# MotorControl_M.net
KiCad netlist of a schematic drawn in EAGLE
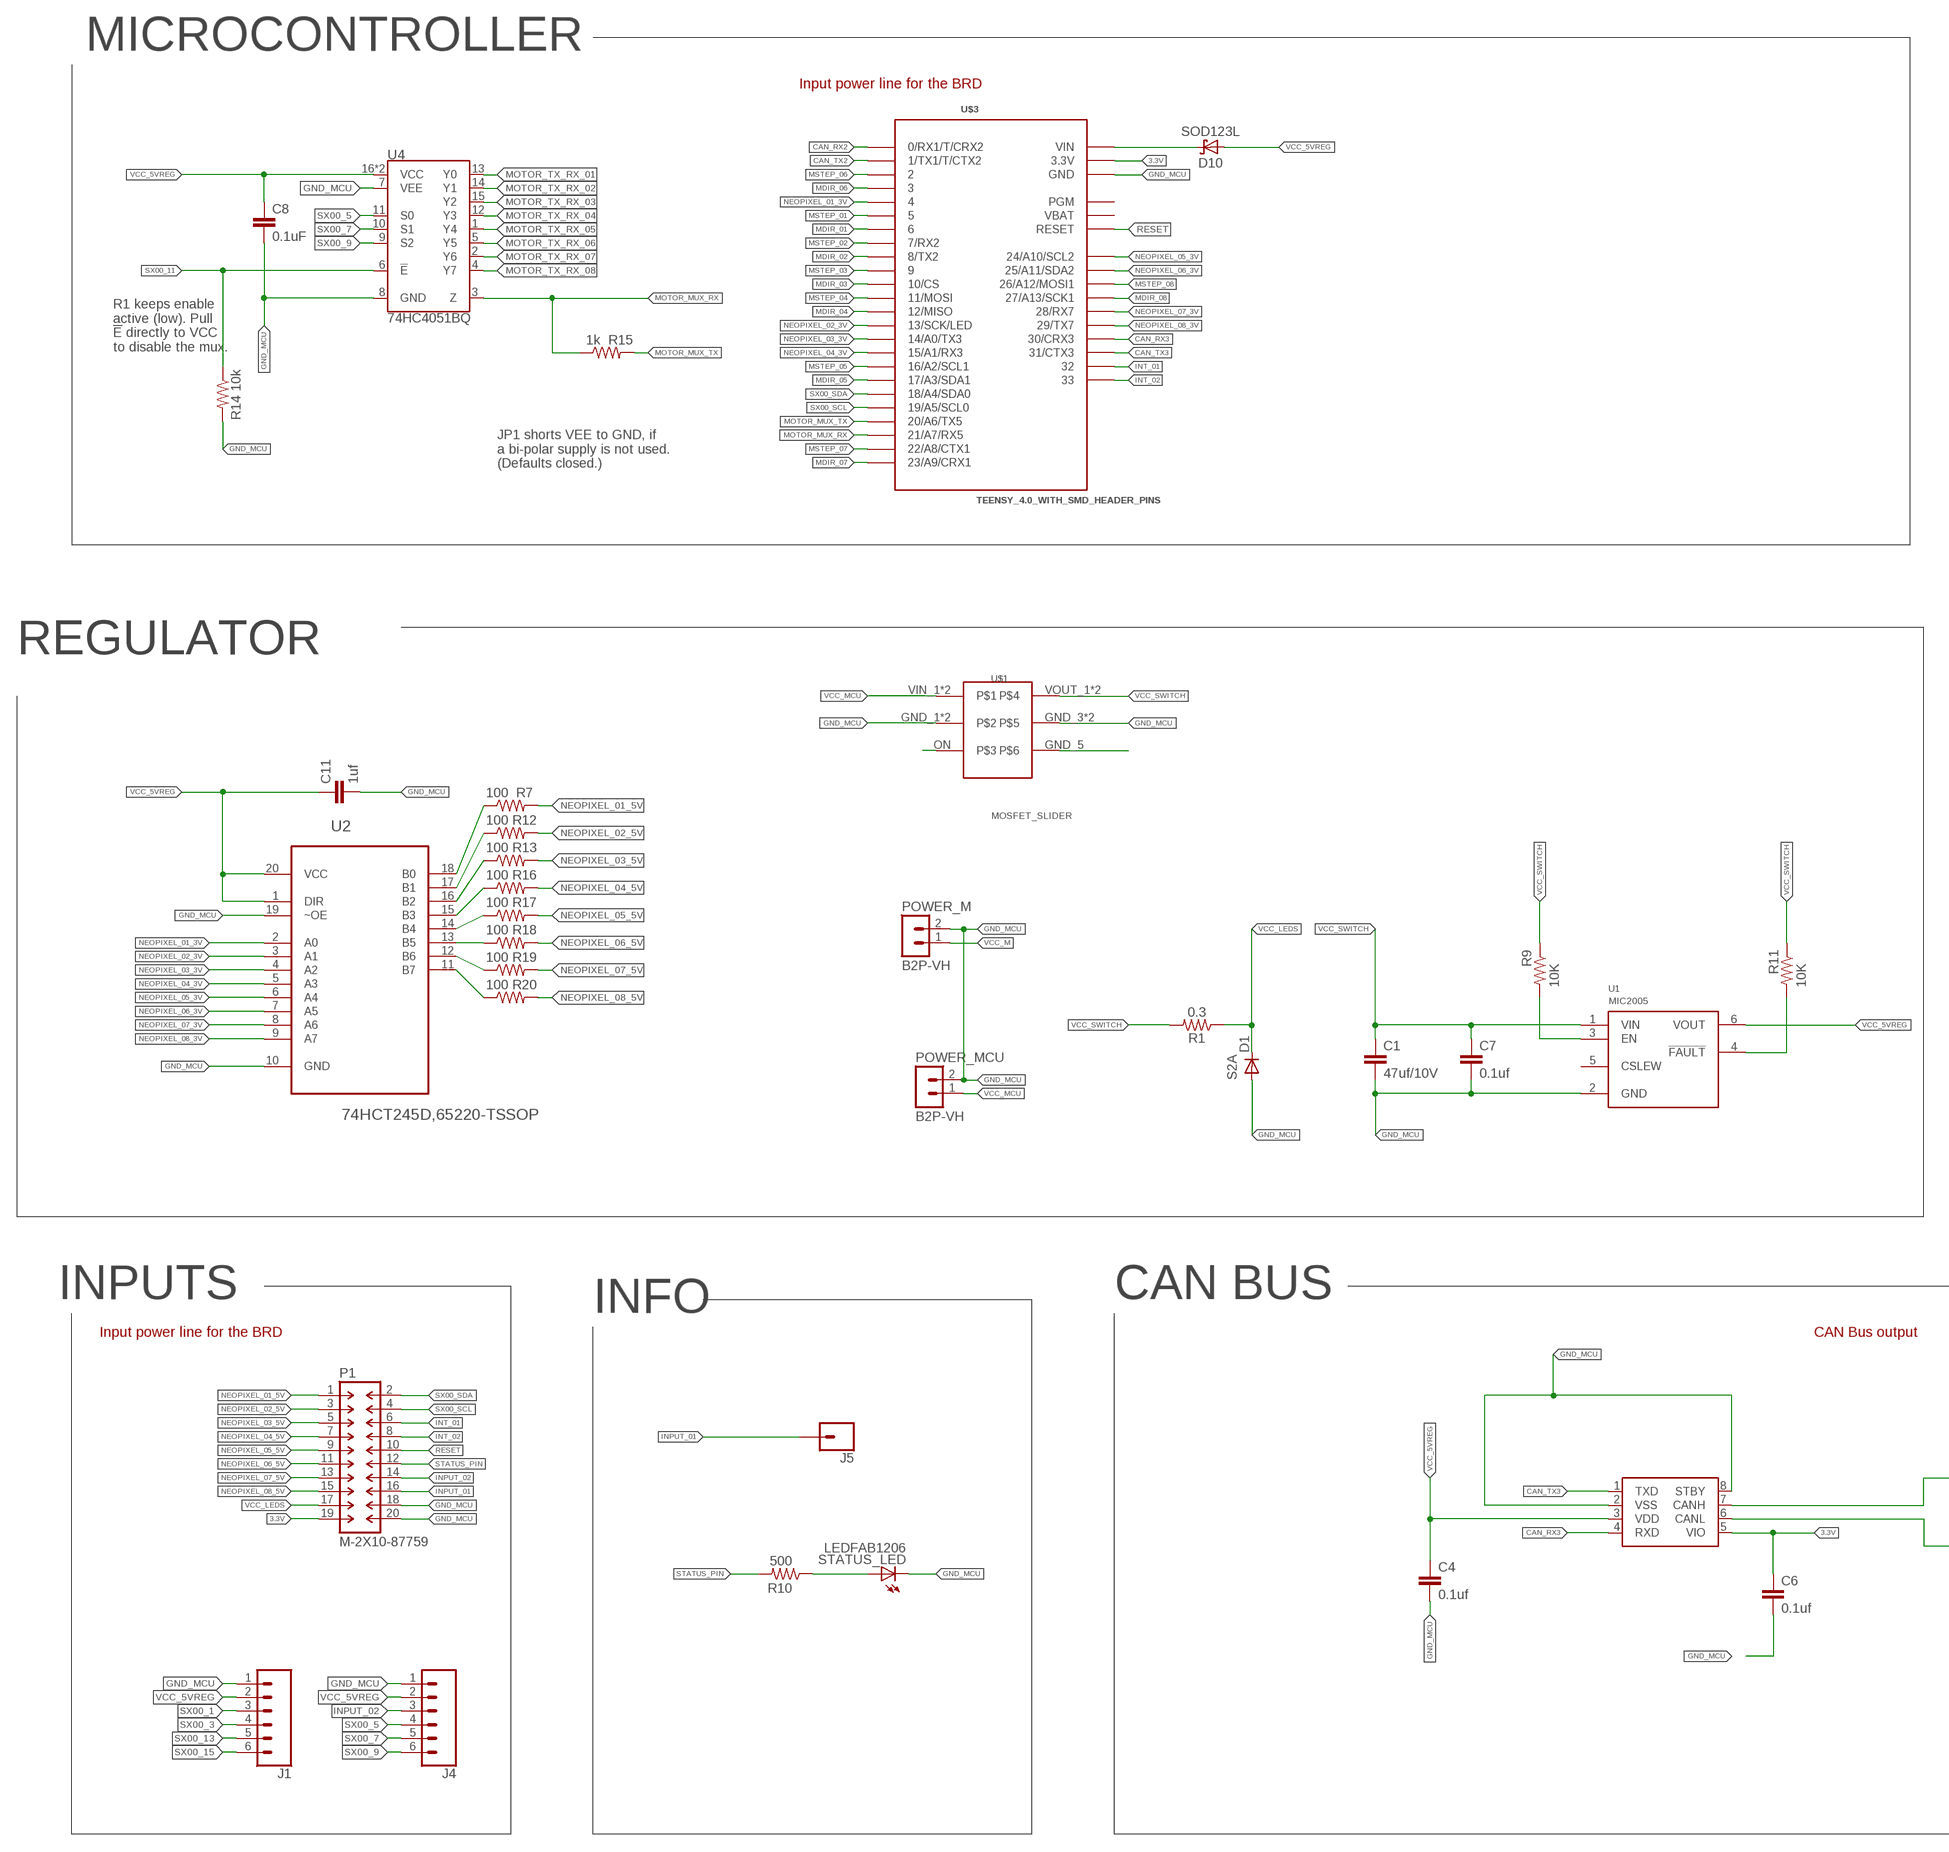
[diagram p0: schematic, sheet 1, part 1 of 3]
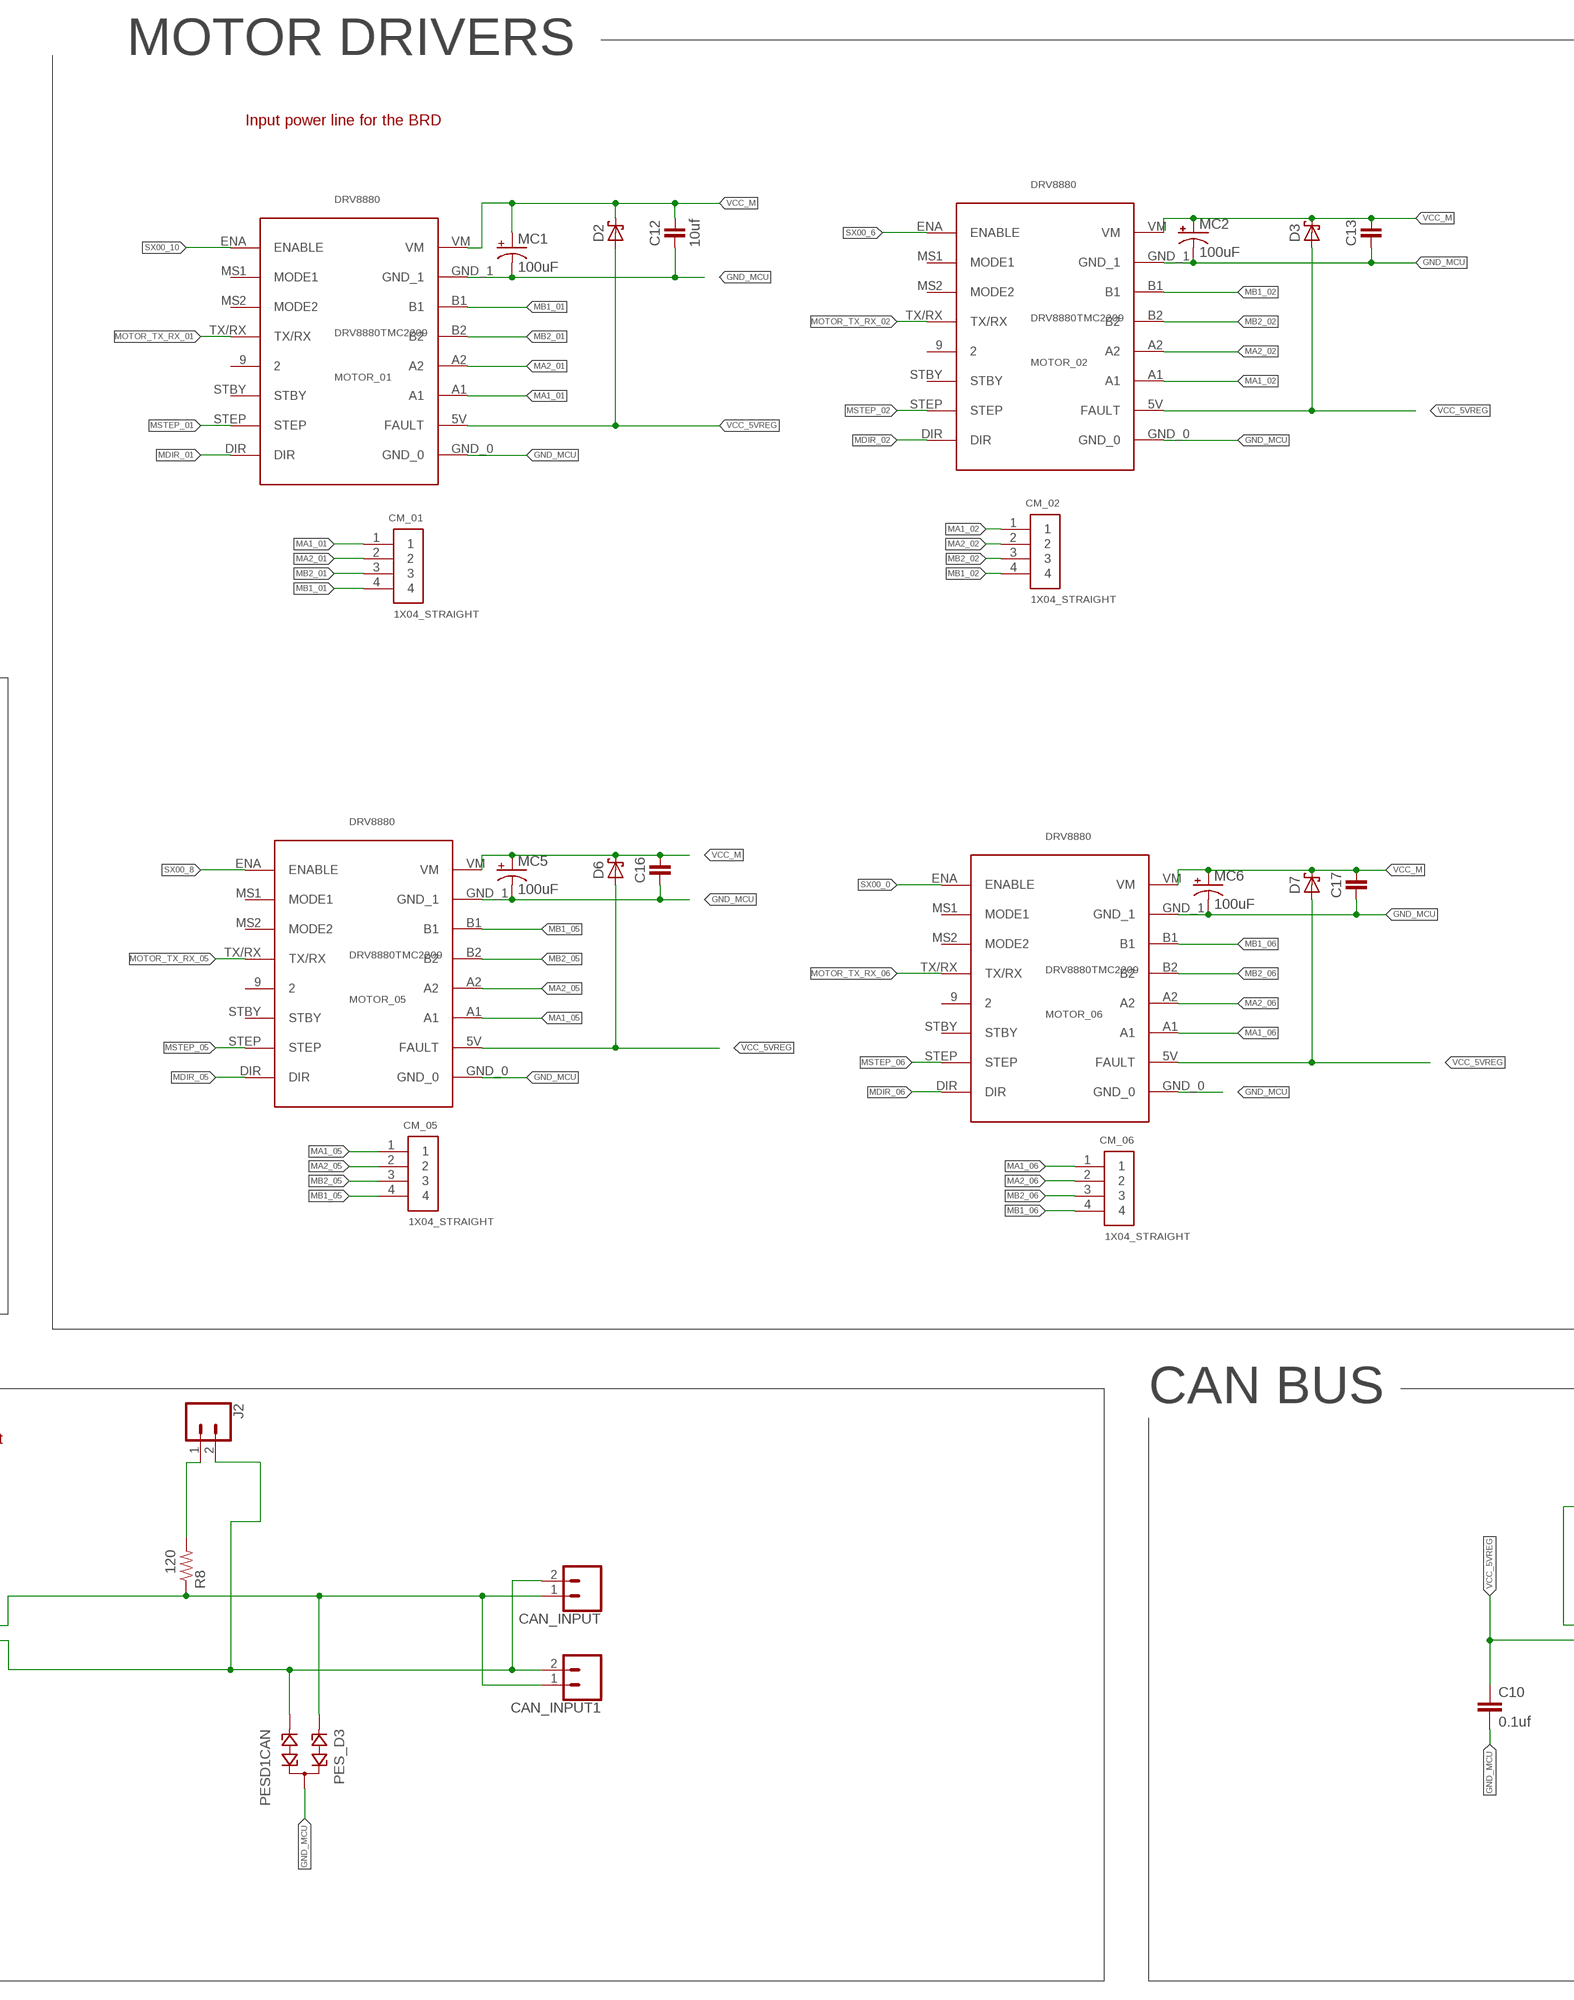
[diagram p1: schematic, sheet 1, part 2 of 3]
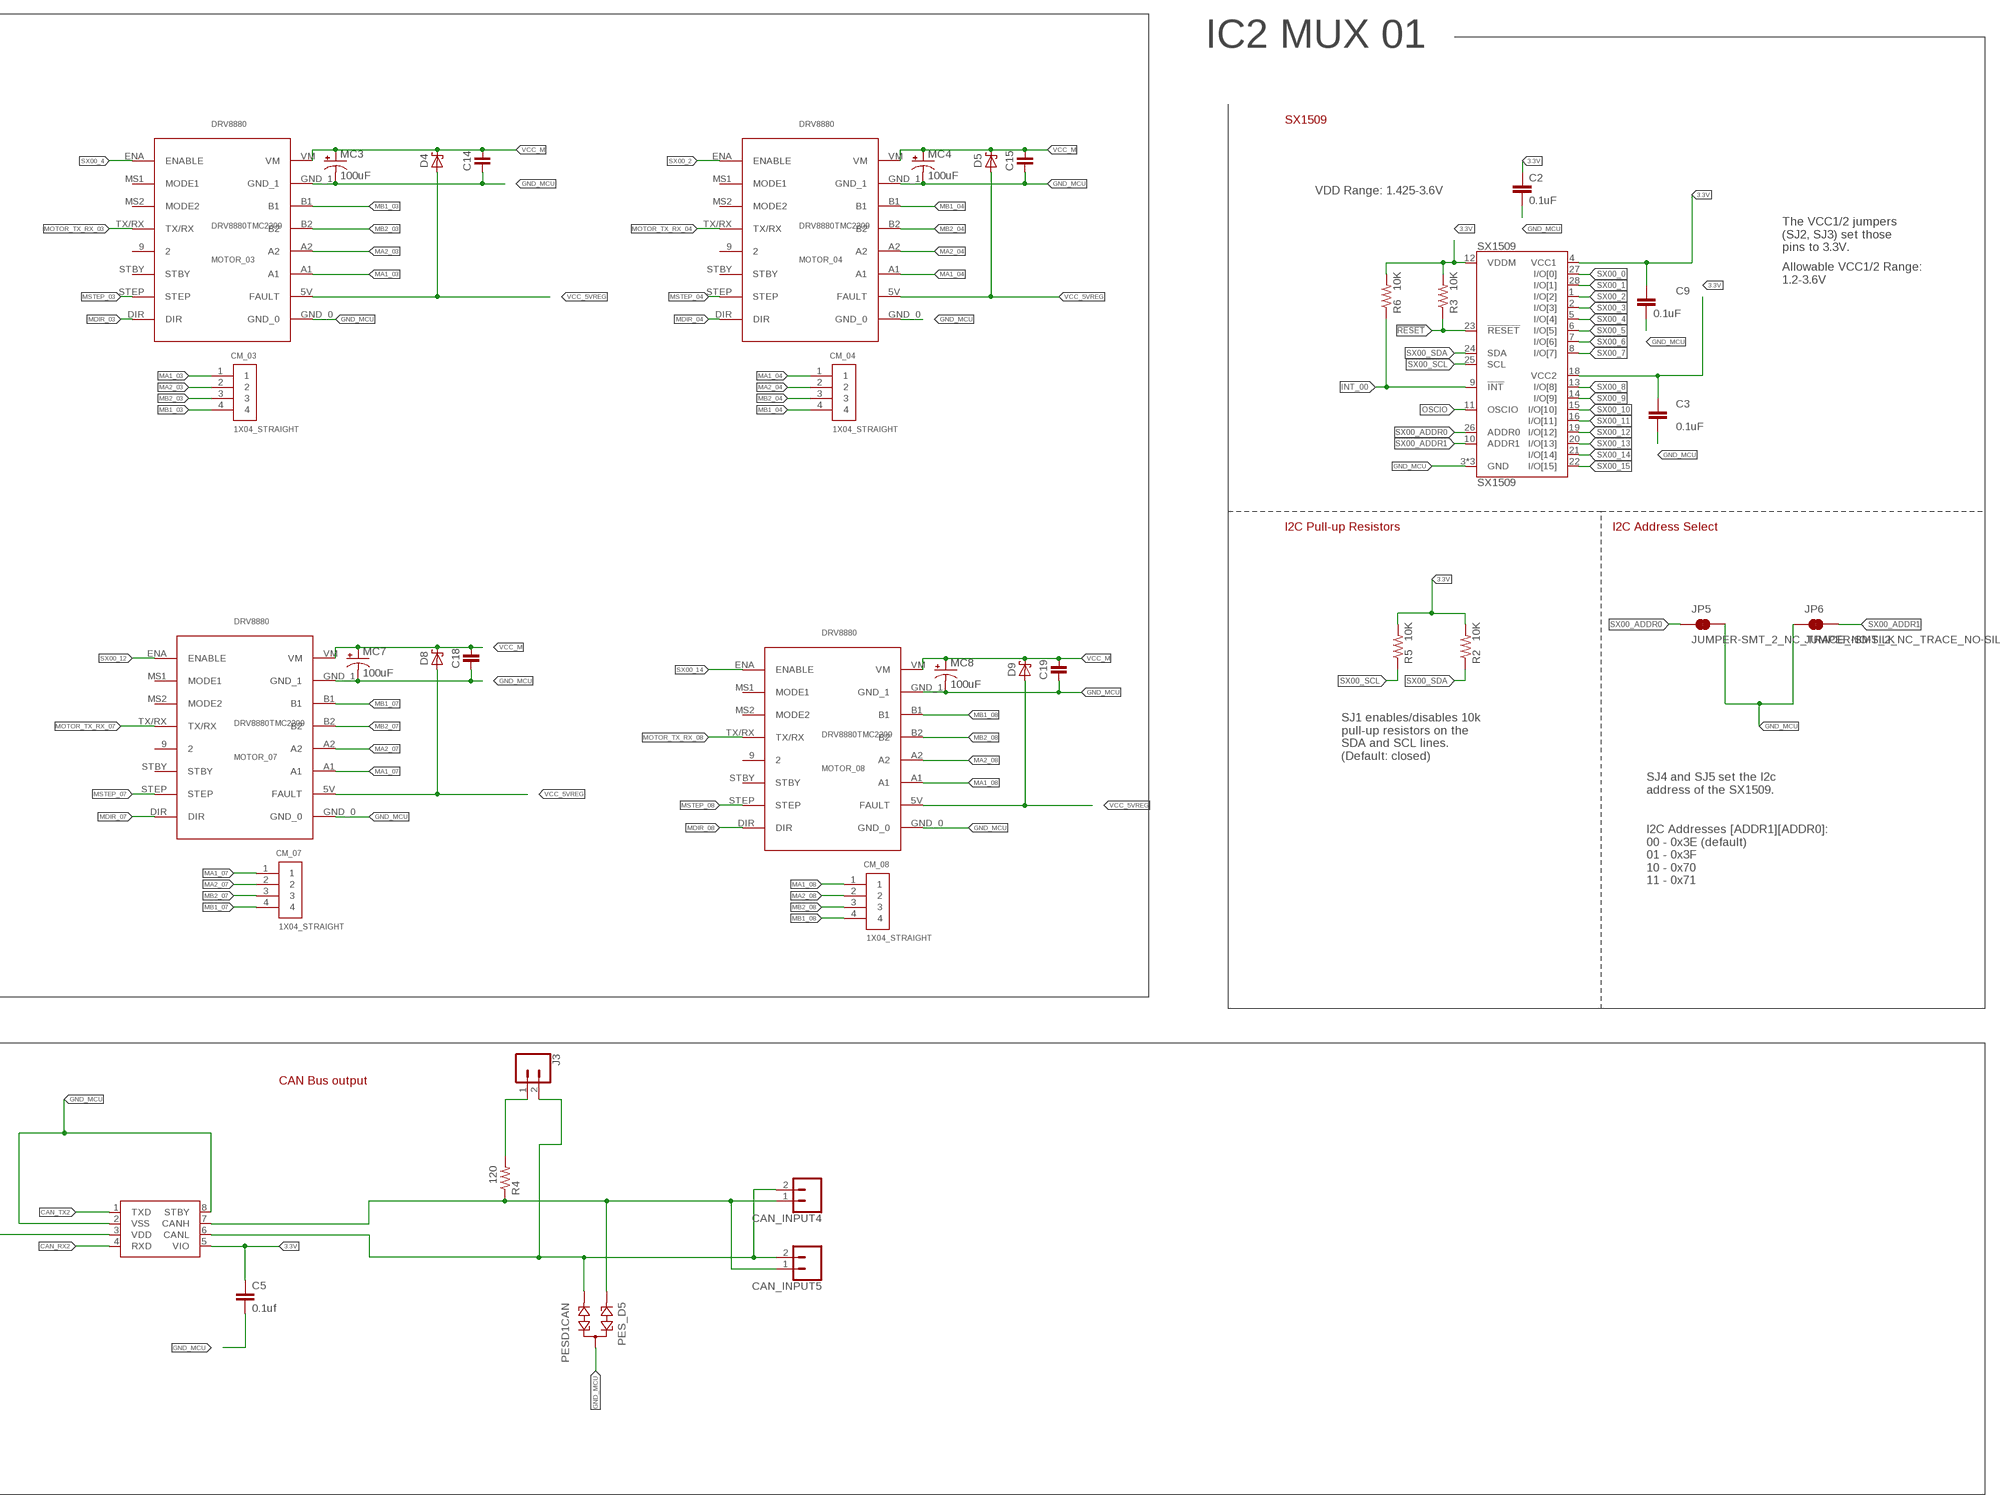
[diagram p2: schematic, sheet 1, part 3 of 3]

(export (version "E")
  (design (tool "Eeschema 10.0.6"))
  (components
    (comp (ref "C1")
      (value "47uf/10V")
      (footprint "eagle-import:0603-CAP")
      (libsource (lib "eagle-import") (part "0.1UF-25V(+80/-20%)(0603)"))
    )
    (comp (ref "C2")
      (value "0.1uF")
      (footprint "eagle-import:0603-CAP")
      (libsource (lib "eagle-import") (part "0.1UF-25V(+80/-20%)(0603)"))
    )
    (comp (ref "C3")
      (value "0.1uF")
      (footprint "eagle-import:0603-CAP")
      (libsource (lib "eagle-import") (part "0.1UF-25V(+80/-20%)(0603)"))
    )
    (comp (ref "C4")
      (value "0.1uf")
      (footprint "eagle-import:0603-CAP")
      (libsource (lib "eagle-import") (part "0.1UF-25V(+80/-20%)(0603)"))
    )
    (comp (ref "C5")
      (value "0.1uf")
      (footprint "eagle-import:0603-CAP")
      (libsource (lib "eagle-import") (part "0.1UF-25V(+80/-20%)(0603)"))
    )
    (comp (ref "C6")
      (value "0.1uf")
      (footprint "eagle-import:0603-CAP")
      (libsource (lib "eagle-import") (part "0.1UF-25V(+80/-20%)(0603)"))
    )
    (comp (ref "C7")
      (value "0.1uf")
      (footprint "eagle-import:0603-CAP")
      (libsource (lib "eagle-import") (part "0.1UF-25V(+80/-20%)(0603)"))
    )
    (comp (ref "C8")
      (value "0.1uF")
      (footprint "eagle-import:0603")
      (libsource (lib "eagle-import") (part "0.1UF-0603-25V-(+80/-20%)"))
    )
    (comp (ref "C9")
      (value "0.1uF")
      (footprint "eagle-import:0603-CAP")
      (libsource (lib "eagle-import") (part "0.1UF-25V(+80/-20%)(0603)"))
    )
    (comp (ref "C10")
      (value "0.1uf")
      (footprint "eagle-import:0603-CAP")
      (libsource (lib "eagle-import") (part "0.1UF-25V(+80/-20%)(0603)"))
    )
    (comp (ref "C11")
      (value "1uf")
      (footprint "eagle-import:0603-CAP")
      (libsource (lib "eagle-import") (part "0.1UF-25V(+80/-20%)(0603)"))
    )
    (comp (ref "C12")
      (value "10uf")
      (footprint "eagle-import:C1210")
      (libsource (lib "eagle-import") (part "CAPACITOR-1210"))
    )
    (comp (ref "C13")
      (value "CAPACITOR-1210")
      (footprint "eagle-import:C1210")
      (libsource (lib "eagle-import") (part "CAPACITOR-1210"))
    )
    (comp (ref "C14")
      (value "CAPACITOR-1210")
      (footprint "eagle-import:C1210")
      (libsource (lib "eagle-import") (part "CAPACITOR-1210"))
    )
    (comp (ref "C15")
      (value "CAPACITOR-1210")
      (footprint "eagle-import:C1210")
      (libsource (lib "eagle-import") (part "CAPACITOR-1210"))
    )
    (comp (ref "C16")
      (value "CAPACITOR-1210")
      (footprint "eagle-import:C1210")
      (libsource (lib "eagle-import") (part "CAPACITOR-1210"))
    )
    (comp (ref "C17")
      (value "CAPACITOR-1210")
      (footprint "eagle-import:C1210")
      (libsource (lib "eagle-import") (part "CAPACITOR-1210"))
    )
    (comp (ref "C18")
      (value "CAPACITOR-1210")
      (footprint "eagle-import:C1210")
      (libsource (lib "eagle-import") (part "CAPACITOR-1210"))
    )
    (comp (ref "C19")
      (value "CAPACITOR-1210")
      (footprint "eagle-import:C1210")
      (libsource (lib "eagle-import") (part "CAPACITOR-1210"))
    )
    (comp (ref "CAN_INPUT")
      (value "CONN_02-JST-2MM-SMT")
      (footprint "eagle-import:JST-2-SMD")
      (libsource (lib "eagle-import") (part "CONN_02-JST-2MM-SMT"))
    )
    (comp (ref "CAN_INPUT1")
      (value "CONN_02-JST-2MM-SMT")
      (footprint "eagle-import:JST-2-SMD")
      (libsource (lib "eagle-import") (part "CONN_02-JST-2MM-SMT"))
    )
    (comp (ref "CAN_INPUT4")
      (value "CONN_02-JST-2MM-SMT")
      (footprint "eagle-import:JST-2-SMD")
      (libsource (lib "eagle-import") (part "CONN_02-JST-2MM-SMT"))
    )
    (comp (ref "CAN_INPUT5")
      (value "CONN_02-JST-2MM-SMT")
      (footprint "eagle-import:JST-2-SMD")
      (libsource (lib "eagle-import") (part "CONN_02-JST-2MM-SMT"))
    )
    (comp (ref "CM_01")
      (value "1X04_STRAIGHT")
      (footprint "eagle-import:1X04-CLEANBIG")
      (libsource (lib "eagle-import") (part "1X4-CLEANBIG"))
    )
    (comp (ref "CM_02")
      (value "1X04_STRAIGHT")
      (footprint "eagle-import:1X04-CLEANBIG")
      (libsource (lib "eagle-import") (part "1X4-CLEANBIG"))
    )
    (comp (ref "CM_03")
      (value "1X04_STRAIGHT")
      (footprint "eagle-import:1X04-CLEANBIG")
      (libsource (lib "eagle-import") (part "1X4-CLEANBIG"))
    )
    (comp (ref "CM_04")
      (value "1X04_STRAIGHT")
      (footprint "eagle-import:1X04-CLEANBIG")
      (libsource (lib "eagle-import") (part "1X4-CLEANBIG"))
    )
    (comp (ref "CM_05")
      (value "1X04_STRAIGHT")
      (footprint "eagle-import:1X04-CLEANBIG")
      (libsource (lib "eagle-import") (part "1X4-CLEANBIG"))
    )
    (comp (ref "CM_06")
      (value "1X04_STRAIGHT")
      (footprint "eagle-import:1X04-CLEANBIG")
      (libsource (lib "eagle-import") (part "1X4-CLEANBIG"))
    )
    (comp (ref "CM_07")
      (value "1X04_STRAIGHT")
      (footprint "eagle-import:1X04-CLEANBIG")
      (libsource (lib "eagle-import") (part "1X4-CLEANBIG"))
    )
    (comp (ref "CM_08")
      (value "1X04_STRAIGHT")
      (footprint "eagle-import:1X04-CLEANBIG")
      (libsource (lib "eagle-import") (part "1X4-CLEANBIG"))
    )
    (comp (ref "D1")
      (value "S2A")
      (footprint "eagle-import:DO214AA")
      (fields (field (name "MF") "Fairchild"))
      (libsource (lib "eagle-import") (part "S2A"))
    )
    (comp (ref "D2")
      (value "D_SCHOTTKY-SOD123")
      (footprint "eagle-import:SOD123")
      (libsource (lib "eagle-import") (part "D_SCHOTTKY-SOD123"))
    )
    (comp (ref "D3")
      (value "D_SCHOTTKY-SOD123")
      (footprint "eagle-import:SOD123")
      (libsource (lib "eagle-import") (part "D_SCHOTTKY-SOD123"))
    )
    (comp (ref "D4")
      (value "D_SCHOTTKY-SOD123")
      (footprint "eagle-import:SOD123")
      (libsource (lib "eagle-import") (part "D_SCHOTTKY-SOD123"))
    )
    (comp (ref "D5")
      (value "D_SCHOTTKY-SOD123")
      (footprint "eagle-import:SOD123")
      (libsource (lib "eagle-import") (part "D_SCHOTTKY-SOD123"))
    )
    (comp (ref "D6")
      (value "D_SCHOTTKY-SOD123")
      (footprint "eagle-import:SOD123")
      (libsource (lib "eagle-import") (part "D_SCHOTTKY-SOD123"))
    )
    (comp (ref "D7")
      (value "D_SCHOTTKY-SOD123")
      (footprint "eagle-import:SOD123")
      (libsource (lib "eagle-import") (part "D_SCHOTTKY-SOD123"))
    )
    (comp (ref "D8")
      (value "D_SCHOTTKY-SOD123")
      (footprint "eagle-import:SOD123")
      (libsource (lib "eagle-import") (part "D_SCHOTTKY-SOD123"))
    )
    (comp (ref "D9")
      (value "D_SCHOTTKY-SOD123")
      (footprint "eagle-import:SOD123")
      (libsource (lib "eagle-import") (part "D_SCHOTTKY-SOD123"))
    )
    (comp (ref "D10")
      (value "SOD123L")
      (footprint "eagle-import:SOD123")
      (libsource (lib "eagle-import") (part "D_SCHOTTKY-SOD123"))
    )
    (comp (ref "J1")
      (value "CONN_06SMD-1MM")
      (footprint "eagle-import:1X06-1MM")
      (libsource (lib "eagle-import") (part "CONN_06SMD-1MM"))
    )
    (comp (ref "J2")
      (value "CONN_02")
      (footprint "eagle-import:1X02")
      (libsource (lib "eagle-import") (part "CONN_02"))
    )
    (comp (ref "J3")
      (value "CONN_02")
      (footprint "eagle-import:1X02")
      (libsource (lib "eagle-import") (part "CONN_02"))
    )
    (comp (ref "J4")
      (value "CONN_06SMD-1MM")
      (footprint "eagle-import:1X06-1MM")
      (libsource (lib "eagle-import") (part "CONN_06SMD-1MM"))
    )
    (comp (ref "J5")
      (value "CONN_01")
      (footprint "eagle-import:1X01")
      (libsource (lib "eagle-import") (part "CONN_01"))
    )
    (comp (ref "JP5")
      (value "JUMPER-SMT_2_NC_TRACE_NO-SILK")
      (footprint "eagle-import:SMT-JUMPER_2_NC_TRACE_NO-SILK")
      (libsource (lib "eagle-import") (part "JUMPER-SMT_2_NC_TRACE_NO-SILK"))
    )
    (comp (ref "JP6")
      (value "JUMPER-SMT_2_NC_TRACE_NO-SILK")
      (footprint "eagle-import:SMT-JUMPER_2_NC_TRACE_NO-SILK")
      (libsource (lib "eagle-import") (part "JUMPER-SMT_2_NC_TRACE_NO-SILK"))
    )
    (comp (ref "MC1")
      (value "100uF")
      (footprint "eagle-import:PANASONIC_D")
      (libsource (lib "eagle-import") (part "100UF-POLAR-25V-20%(ELEC)"))
    )
    (comp (ref "MC2")
      (value "100uF")
      (footprint "eagle-import:PANASONIC_D")
      (libsource (lib "eagle-import") (part "100UF-POLAR-25V-20%(ELEC)"))
    )
    (comp (ref "MC3")
      (value "100uF")
      (footprint "eagle-import:PANASONIC_D")
      (libsource (lib "eagle-import") (part "100UF-POLAR-25V-20%(ELEC)"))
    )
    (comp (ref "MC4")
      (value "100uF")
      (footprint "eagle-import:PANASONIC_D")
      (libsource (lib "eagle-import") (part "100UF-POLAR-25V-20%(ELEC)"))
    )
    (comp (ref "MC5")
      (value "100uF")
      (footprint "eagle-import:PANASONIC_D")
      (libsource (lib "eagle-import") (part "100UF-POLAR-25V-20%(ELEC)"))
    )
    (comp (ref "MC6")
      (value "100uF")
      (footprint "eagle-import:PANASONIC_D")
      (libsource (lib "eagle-import") (part "100UF-POLAR-25V-20%(ELEC)"))
    )
    (comp (ref "MC7")
      (value "100uF")
      (footprint "eagle-import:PANASONIC_D")
      (libsource (lib "eagle-import") (part "100UF-POLAR-25V-20%(ELEC)"))
    )
    (comp (ref "MC8")
      (value "100uF")
      (footprint "eagle-import:PANASONIC_D")
      (libsource (lib "eagle-import") (part "100UF-POLAR-25V-20%(ELEC)"))
    )
    (comp (ref "MCP2562FD")
      (value "MCP2562-E/SN")
      (footprint "eagle-import:SOIC127P600X175-8N")
      (fields (field (name "MF") "Microchip"))
      (libsource (lib "eagle-import") (part "MCP2562-E/SN"))
    )
    (comp (ref "MCP2562_2.0")
      (value "MCP2562-E/SN")
      (footprint "eagle-import:SOIC127P600X175-8N")
      (fields (field (name "MF") "Microchip"))
      (libsource (lib "eagle-import") (part "MCP2562-E/SN"))
    )
    (comp (ref "MOTOR_01")
      (value "DRV8880TMC2209")
      (footprint "eagle-import:TMC2209_SMD")
      (libsource (lib "eagle-import") (part "DRV8880TMC2209"))
    )
    (comp (ref "MOTOR_02")
      (value "DRV8880TMC2209")
      (footprint "eagle-import:TMC2209_SMD")
      (libsource (lib "eagle-import") (part "DRV8880TMC2209"))
    )
    (comp (ref "MOTOR_03")
      (value "DRV8880TMC2209")
      (footprint "eagle-import:TMC2209_SMD")
      (libsource (lib "eagle-import") (part "DRV8880TMC2209"))
    )
    (comp (ref "MOTOR_04")
      (value "DRV8880TMC2209")
      (footprint "eagle-import:TMC2209_SMD")
      (libsource (lib "eagle-import") (part "DRV8880TMC2209"))
    )
    (comp (ref "MOTOR_05")
      (value "DRV8880TMC2209")
      (footprint "eagle-import:TMC2209_SMD")
      (libsource (lib "eagle-import") (part "DRV8880TMC2209"))
    )
    (comp (ref "MOTOR_06")
      (value "DRV8880TMC2209")
      (footprint "eagle-import:TMC2209_SMD")
      (libsource (lib "eagle-import") (part "DRV8880TMC2209"))
    )
    (comp (ref "MOTOR_07")
      (value "DRV8880TMC2209")
      (footprint "eagle-import:TMC2209_SMD")
      (libsource (lib "eagle-import") (part "DRV8880TMC2209"))
    )
    (comp (ref "MOTOR_08")
      (value "DRV8880TMC2209")
      (footprint "eagle-import:TMC2209_SMD")
      (libsource (lib "eagle-import") (part "DRV8880TMC2209"))
    )
    (comp (ref "P1")
      (value "M-2X10-87759")
      (footprint "eagle-import:87759-20")
      (libsource (lib "eagle-import") (part "M-2X10-87759"))
    )
    (comp (ref "PES_D3")
      (value "PESD1CAN")
      (footprint "eagle-import:SOT23")
      (libsource (lib "eagle-import") (part "PESD1CAN"))
    )
    (comp (ref "PES_D5")
      (value "PESD1CAN")
      (footprint "eagle-import:SOT23")
      (libsource (lib "eagle-import") (part "PESD1CAN"))
    )
    (comp (ref "POWER_M")
      (value "B2P-VH")
      (footprint "eagle-import:B2P-VH")
      (libsource (lib "eagle-import") (part "B2P-VH"))
    )
    (comp (ref "POWER_MCU")
      (value "B2P-VH")
      (footprint "eagle-import:B2P-VH")
      (libsource (lib "eagle-import") (part "B2P-VH"))
    )
    (comp (ref "R1")
      (value "0.3")
      (footprint "eagle-import:0805")
      (libsource (lib "eagle-import") (part "0.3OHM-0805-1/8W-1%"))
    )
    (comp (ref "R2")
      (value "10K")
      (footprint "eagle-import:0603-RES")
      (libsource (lib "eagle-import") (part "10KOHM-1/10W-1%(0603)0603"))
    )
    (comp (ref "R3")
      (value "10K")
      (footprint "eagle-import:0603-RES")
      (libsource (lib "eagle-import") (part "10KOHM-1/10W-1%(0603)0603"))
    )
    (comp (ref "R4")
      (value "120")
      (footprint "eagle-import:0603-RES")
      (libsource (lib "eagle-import") (part "SparkFun-Resistors_532_10KOHM-1/10W-1%(0603)0603"))
    )
    (comp (ref "R5")
      (value "10K")
      (footprint "eagle-import:0603-RES")
      (libsource (lib "eagle-import") (part "10KOHM-1/10W-1%(0603)0603"))
    )
    (comp (ref "R6")
      (value "10K")
      (footprint "eagle-import:0603-RES")
      (libsource (lib "eagle-import") (part "10KOHM-1/10W-1%(0603)0603"))
    )
    (comp (ref "R7")
      (value "100")
      (footprint "eagle-import:0603")
      (libsource (lib "eagle-import") (part "10KOHM-0603-1/10W-1%"))
    )
    (comp (ref "R8")
      (value "120")
      (footprint "eagle-import:0603-RES")
      (libsource (lib "eagle-import") (part "SparkFun-Resistors_532_10KOHM-1/10W-1%(0603)0603"))
    )
    (comp (ref "R9")
      (value "10K")
      (footprint "eagle-import:0603-RES")
      (libsource (lib "eagle-import") (part "SparkFun-Resistors_532_10KOHM-1/10W-1%(0603)0603"))
    )
    (comp (ref "R10")
      (value "500")
      (footprint "eagle-import:0603-RES")
      (libsource (lib "eagle-import") (part "SparkFun-Resistors_532_10KOHM-1/10W-1%(0603)0603"))
    )
    (comp (ref "R11")
      (value "10K")
      (footprint "eagle-import:0603-RES")
      (libsource (lib "eagle-import") (part "SparkFun-Resistors_532_10KOHM-1/10W-1%(0603)0603"))
    )
    (comp (ref "R12")
      (value "100")
      (footprint "eagle-import:0603")
      (libsource (lib "eagle-import") (part "10KOHM-0603-1/10W-1%"))
    )
    (comp (ref "R13")
      (value "100")
      (footprint "eagle-import:0603")
      (libsource (lib "eagle-import") (part "10KOHM-0603-1/10W-1%"))
    )
    (comp (ref "R14")
      (value "10k")
      (footprint "eagle-import:0603")
      (libsource (lib "eagle-import") (part "10KOHM-0603-1/10W-1%"))
    )
    (comp (ref "R15")
      (value "1k")
      (footprint "eagle-import:0603")
      (libsource (lib "eagle-import") (part "10KOHM-0603-1/10W-1%"))
    )
    (comp (ref "R16")
      (value "100")
      (footprint "eagle-import:0603")
      (libsource (lib "eagle-import") (part "10KOHM-0603-1/10W-1%"))
    )
    (comp (ref "R17")
      (value "100")
      (footprint "eagle-import:0603")
      (libsource (lib "eagle-import") (part "10KOHM-0603-1/10W-1%"))
    )
    (comp (ref "R18")
      (value "100")
      (footprint "eagle-import:0603")
      (libsource (lib "eagle-import") (part "10KOHM-0603-1/10W-1%"))
    )
    (comp (ref "R19")
      (value "100")
      (footprint "eagle-import:0603")
      (libsource (lib "eagle-import") (part "10KOHM-0603-1/10W-1%"))
    )
    (comp (ref "R20")
      (value "100")
      (footprint "eagle-import:0603")
      (libsource (lib "eagle-import") (part "10KOHM-0603-1/10W-1%"))
    )
    (comp (ref "STATUS_LED")
      (value "LEDFAB1206")
      (footprint "eagle-import:LED1206FAB")
      (libsource (lib "eagle-import") (part "LEDFAB1206"))
    )
    (comp (ref "SX1509")
      (value "SX1509")
      (footprint "eagle-import:QFN-28")
      (libsource (lib "eagle-import") (part "SX1509"))
    )
    (comp (ref "U$1")
      (value "MOSFET_SLIDER")
      (footprint "eagle-import:MOSFET_SLIDER")
      (libsource (lib "eagle-import") (part "MOSFET_SLIDER"))
    )
    (comp (ref "U$3")
      (value "TEENSY_4.0_WITH_SMD_HEADER_PINS")
      (footprint "eagle-import:TEENSY_4.0_WITH_SMD_HEADER_PINS")
      (libsource (lib "eagle-import") (part "TEENSY_4.0_WITH_SMD_HEADER_PINS"))
    )
    (comp (ref "U1")
      (value "MIC2005")
      (footprint "eagle-import:SOT23-6")
      (libsource (lib "eagle-import") (part "MIC2050"))
    )
    (comp (ref "U2")
      (value "74HCT245D,65220-TSSOP")
      (footprint "eagle-import:20-TSSOP")
      (libsource (lib "eagle-import") (part "74HCT245D,65220-TSSOP"))
    )
    (comp (ref "U4")
      (value "74HC4051BQ")
      (footprint "eagle-import:DHVQFN-16-2.5X3.5MM")
      (libsource (lib "eagle-import") (part "74HC4051BQ"))
    )
  )
  (nets
    (net (code "1") (name "3.3V") (class "Default")
      (node (ref "C2") (pin "1") (pinfunction "1_1") (pintype "passive"))
      (node (ref "C3") (pin "1") (pinfunction "1_1") (pintype "passive"))
      (node (ref "C5") (pin "1") (pinfunction "1_1") (pintype "passive"))
      (node (ref "C6") (pin "1") (pinfunction "1_1") (pintype "passive"))
      (node (ref "C9") (pin "1") (pinfunction "1_1") (pintype "passive"))
      (node (ref "MCP2562FD") (pin "5") (pinfunction "VIO_5") (pintype "power_in"))
      (node (ref "MCP2562_2.0") (pin "5") (pinfunction "VIO_5") (pintype "power_in"))
      (node (ref "P1") (pin "19") (pinfunction "19_19") (pintype "passive"))
      (node (ref "R2") (pin "2") (pinfunction "2_2") (pintype "passive"))
      (node (ref "R3") (pin "2") (pinfunction "2_2") (pintype "passive"))
      (node (ref "R5") (pin "2") (pinfunction "2_2") (pintype "passive"))
      (node (ref "R6") (pin "2") (pinfunction "2_2") (pintype "passive"))
      (node (ref "SX1509") (pin "12") (pinfunction "VDDM_12") (pintype "bidirectional"))
      (node (ref "SX1509") (pin "18") (pinfunction "VCC2_18") (pintype "bidirectional"))
      (node (ref "SX1509") (pin "4") (pinfunction "VCC1_4") (pintype "bidirectional"))
      (node (ref "U$3") (pin "3.3V") (pinfunction "3.3V_3.3V") (pintype "power_in"))
      (node (ref "U$3") (pin "3.3V1") (pinfunction "3.3V_3.3V1") (pintype "power_in"))
    )
    (net (code "2") (name "CAN_RX2") (class "Default")
      (node (ref "MCP2562_2.0") (pin "4") (pinfunction "RXD_4") (pintype "output"))
      (node (ref "U$3") (pin "0") (pinfunction "0/RX1/T/CRX2_0") (pintype "bidirectional"))
    )
    (net (code "3") (name "CAN_RX3") (class "Default")
      (node (ref "MCP2562FD") (pin "4") (pinfunction "RXD_4") (pintype "output"))
      (node (ref "U$3") (pin "30") (pinfunction "30/CRX3_30") (pintype "bidirectional"))
    )
    (net (code "4") (name "CAN_TX2") (class "Default")
      (node (ref "MCP2562_2.0") (pin "1") (pinfunction "TXD_1") (pintype "input"))
      (node (ref "U$3") (pin "1") (pinfunction "1/TX1/T/CTX2_1") (pintype "bidirectional"))
    )
    (net (code "5") (name "CAN_TX3") (class "Default")
      (node (ref "MCP2562FD") (pin "1") (pinfunction "TXD_1") (pintype "input"))
      (node (ref "U$3") (pin "31") (pinfunction "31/CTX3_31") (pintype "bidirectional"))
    )
    (net (code "6") (name "GND_MCU") (class "Default")
      (node (ref "C1") (pin "2") (pinfunction "2_2") (pintype "passive"))
      (node (ref "C10") (pin "2") (pinfunction "2_2") (pintype "passive"))
      (node (ref "C11") (pin "2") (pinfunction "2_2") (pintype "passive"))
      (node (ref "C12") (pin "1") (pinfunction "1_1") (pintype "passive"))
      (node (ref "C13") (pin "1") (pinfunction "1_1") (pintype "passive"))
      (node (ref "C14") (pin "1") (pinfunction "1_1") (pintype "passive"))
      (node (ref "C15") (pin "1") (pinfunction "1_1") (pintype "passive"))
      (node (ref "C16") (pin "1") (pinfunction "1_1") (pintype "passive"))
      (node (ref "C17") (pin "1") (pinfunction "1_1") (pintype "passive"))
      (node (ref "C18") (pin "1") (pinfunction "1_1") (pintype "passive"))
      (node (ref "C19") (pin "1") (pinfunction "1_1") (pintype "passive"))
      (node (ref "C2") (pin "2") (pinfunction "2_2") (pintype "passive"))
      (node (ref "C3") (pin "2") (pinfunction "2_2") (pintype "passive"))
      (node (ref "C4") (pin "2") (pinfunction "2_2") (pintype "passive"))
      (node (ref "C5") (pin "2") (pinfunction "2_2") (pintype "passive"))
      (node (ref "C6") (pin "2") (pinfunction "2_2") (pintype "passive"))
      (node (ref "C7") (pin "2") (pinfunction "2_2") (pintype "passive"))
      (node (ref "C8") (pin "2") (pinfunction "2_2") (pintype "passive"))
      (node (ref "C9") (pin "2") (pinfunction "2_2") (pintype "passive"))
      (node (ref "D1") (pin "A") (pinfunction "A_A") (pintype "passive"))
      (node (ref "J1") (pin "1") (pinfunction "1_1") (pintype "passive"))
      (node (ref "J4") (pin "1") (pinfunction "1_1") (pintype "passive"))
      (node (ref "JP5") (pin "2") (pinfunction "2_2") (pintype "passive"))
      (node (ref "JP6") (pin "1") (pinfunction "1_1") (pintype "passive"))
      (node (ref "MC1") (pin "-") (pinfunction "-_-") (pintype "passive"))
      (node (ref "MC2") (pin "-") (pinfunction "-_-") (pintype "passive"))
      (node (ref "MC3") (pin "-") (pinfunction "-_-") (pintype "passive"))
      (node (ref "MC4") (pin "-") (pinfunction "-_-") (pintype "passive"))
      (node (ref "MC5") (pin "-") (pinfunction "-_-") (pintype "passive"))
      (node (ref "MC6") (pin "-") (pinfunction "-_-") (pintype "passive"))
      (node (ref "MC7") (pin "-") (pinfunction "-_-") (pintype "passive"))
      (node (ref "MC8") (pin "-") (pinfunction "-_-") (pintype "passive"))
      (node (ref "MCP2562FD") (pin "2") (pinfunction "VSS_2") (pintype "power_in"))
      (node (ref "MCP2562FD") (pin "8") (pinfunction "STBY_8") (pintype "input"))
      (node (ref "MCP2562_2.0") (pin "2") (pinfunction "VSS_2") (pintype "power_in"))
      (node (ref "MCP2562_2.0") (pin "8") (pinfunction "STBY_8") (pintype "input"))
      (node (ref "MOTOR_01") (pin "GND_0") (pinfunction "GND_0_GND_0") (pintype "bidirectional"))
      (node (ref "MOTOR_01") (pin "GND_1") (pinfunction "GND_1_GND_1") (pintype "bidirectional"))
      (node (ref "MOTOR_02") (pin "GND_0") (pinfunction "GND_0_GND_0") (pintype "bidirectional"))
      (node (ref "MOTOR_02") (pin "GND_1") (pinfunction "GND_1_GND_1") (pintype "bidirectional"))
      (node (ref "MOTOR_03") (pin "GND_0") (pinfunction "GND_0_GND_0") (pintype "bidirectional"))
      (node (ref "MOTOR_03") (pin "GND_1") (pinfunction "GND_1_GND_1") (pintype "bidirectional"))
      (node (ref "MOTOR_04") (pin "GND_0") (pinfunction "GND_0_GND_0") (pintype "bidirectional"))
      (node (ref "MOTOR_04") (pin "GND_1") (pinfunction "GND_1_GND_1") (pintype "bidirectional"))
      (node (ref "MOTOR_05") (pin "GND_0") (pinfunction "GND_0_GND_0") (pintype "bidirectional"))
      (node (ref "MOTOR_05") (pin "GND_1") (pinfunction "GND_1_GND_1") (pintype "bidirectional"))
      (node (ref "MOTOR_06") (pin "GND_0") (pinfunction "GND_0_GND_0") (pintype "bidirectional"))
      (node (ref "MOTOR_06") (pin "GND_1") (pinfunction "GND_1_GND_1") (pintype "bidirectional"))
      (node (ref "MOTOR_07") (pin "GND_0") (pinfunction "GND_0_GND_0") (pintype "bidirectional"))
      (node (ref "MOTOR_07") (pin "GND_1") (pinfunction "GND_1_GND_1") (pintype "bidirectional"))
      (node (ref "MOTOR_08") (pin "GND_0") (pinfunction "GND_0_GND_0") (pintype "bidirectional"))
      (node (ref "MOTOR_08") (pin "GND_1") (pinfunction "GND_1_GND_1") (pintype "bidirectional"))
      (node (ref "P1") (pin "18") (pinfunction "18_18") (pintype "passive"))
      (node (ref "P1") (pin "20") (pinfunction "20_20") (pintype "passive"))
      (node (ref "PES_D3") (pin "3") (pinfunction "3_3") (pintype "passive"))
      (node (ref "PES_D5") (pin "3") (pinfunction "3_3") (pintype "passive"))
      (node (ref "POWER_M") (pin "2") (pinfunction "2_2") (pintype "passive"))
      (node (ref "POWER_MCU") (pin "2") (pinfunction "2_2") (pintype "passive"))
      (node (ref "R14") (pin "2") (pinfunction "2_2") (pintype "passive"))
      (node (ref "STATUS_LED") (pin "2") (pinfunction "C_2") (pintype "passive"))
      (node (ref "SX1509") (pin "17") (pinfunction "GND_17") (pintype "bidirectional"))
      (node (ref "SX1509") (pin "29") (pinfunction "GND_29") (pintype "bidirectional"))
      (node (ref "SX1509") (pin "3") (pinfunction "GND_3") (pintype "bidirectional"))
      (node (ref "U$1") (pin "GND_1") (pinfunction "P$2_GND_1") (pintype "bidirectional"))
      (node (ref "U$1") (pin "GND_2") (pinfunction "P$2_GND_2") (pintype "bidirectional"))
      (node (ref "U$1") (pin "GND_3") (pinfunction "P$5_GND_3") (pintype "bidirectional"))
      (node (ref "U$1") (pin "GND_4") (pinfunction "P$5_GND_4") (pintype "bidirectional"))
      (node (ref "U$3") (pin "GND") (pinfunction "GND_GND") (pintype "power_in"))
      (node (ref "U$3") (pin "GND1") (pinfunction "GND_GND1") (pintype "power_in"))
      (node (ref "U$3") (pin "GND2") (pinfunction "GND_GND2") (pintype "power_in"))
      (node (ref "U1") (pin "2") (pinfunction "GND_2") (pintype "bidirectional"))
      (node (ref "U2") (pin "10") (pinfunction "GND_10") (pintype "passive"))
      (node (ref "U2") (pin "19") (pinfunction "~{OE}_19") (pintype "input"))
      (node (ref "U4") (pin "7") (pinfunction "VEE_7") (pintype "bidirectional"))
      (node (ref "U4") (pin "8") (pinfunction "GND_8") (pintype "bidirectional"))
    )
    (net (code "7") (name "INPUT_01") (class "Default")
      (node (ref "J5") (pin "1") (pinfunction "1_1") (pintype "passive"))
      (node (ref "P1") (pin "16") (pinfunction "16_16") (pintype "passive"))
    )
    (net (code "8") (name "INPUT_02") (class "Default")
      (node (ref "J4") (pin "3") (pinfunction "3_3") (pintype "passive"))
      (node (ref "P1") (pin "14") (pinfunction "14_14") (pintype "passive"))
    )
    (net (code "9") (name "INT_00") (class "Default")
      (node (ref "R6") (pin "1") (pinfunction "1_1") (pintype "passive"))
      (node (ref "SX1509") (pin "9") (pinfunction "~{INT}_9") (pintype "bidirectional"))
    )
    (net (code "10") (name "INT_01") (class "Default")
      (node (ref "P1") (pin "6") (pinfunction "6_6") (pintype "passive"))
      (node (ref "U$3") (pin "32") (pinfunction "32_32") (pintype "bidirectional"))
    )
    (net (code "11") (name "INT_02") (class "Default")
      (node (ref "P1") (pin "8") (pinfunction "8_8") (pintype "passive"))
      (node (ref "U$3") (pin "33") (pinfunction "33_33") (pintype "bidirectional"))
    )
    (net (code "12") (name "MA1_01") (class "Default")
      (node (ref "CM_01") (pin "1") (pinfunction "1_1") (pintype "bidirectional"))
      (node (ref "MOTOR_01") (pin "A1") (pinfunction "A1_A1") (pintype "bidirectional"))
    )
    (net (code "13") (name "MA1_02") (class "Default")
      (node (ref "CM_02") (pin "1") (pinfunction "1_1") (pintype "bidirectional"))
      (node (ref "MOTOR_02") (pin "A1") (pinfunction "A1_A1") (pintype "bidirectional"))
    )
    (net (code "14") (name "MA1_03") (class "Default")
      (node (ref "CM_03") (pin "1") (pinfunction "1_1") (pintype "bidirectional"))
      (node (ref "MOTOR_03") (pin "A1") (pinfunction "A1_A1") (pintype "bidirectional"))
    )
    (net (code "15") (name "MA1_04") (class "Default")
      (node (ref "CM_04") (pin "1") (pinfunction "1_1") (pintype "bidirectional"))
      (node (ref "MOTOR_04") (pin "A1") (pinfunction "A1_A1") (pintype "bidirectional"))
    )
    (net (code "16") (name "MA1_05") (class "Default")
      (node (ref "CM_05") (pin "1") (pinfunction "1_1") (pintype "bidirectional"))
      (node (ref "MOTOR_05") (pin "A1") (pinfunction "A1_A1") (pintype "bidirectional"))
    )
    (net (code "17") (name "MA1_06") (class "Default")
      (node (ref "CM_06") (pin "1") (pinfunction "1_1") (pintype "bidirectional"))
      (node (ref "MOTOR_06") (pin "A1") (pinfunction "A1_A1") (pintype "bidirectional"))
    )
    (net (code "18") (name "MA1_07") (class "Default")
      (node (ref "CM_07") (pin "1") (pinfunction "1_1") (pintype "bidirectional"))
      (node (ref "MOTOR_07") (pin "A1") (pinfunction "A1_A1") (pintype "bidirectional"))
    )
    (net (code "19") (name "MA1_08") (class "Default")
      (node (ref "CM_08") (pin "1") (pinfunction "1_1") (pintype "bidirectional"))
      (node (ref "MOTOR_08") (pin "A1") (pinfunction "A1_A1") (pintype "bidirectional"))
    )
    (net (code "20") (name "MA2_01") (class "Default")
      (node (ref "CM_01") (pin "2") (pinfunction "2_2") (pintype "bidirectional"))
      (node (ref "MOTOR_01") (pin "A2") (pinfunction "A2_A2") (pintype "bidirectional"))
    )
    (net (code "21") (name "MA2_02") (class "Default")
      (node (ref "CM_02") (pin "2") (pinfunction "2_2") (pintype "bidirectional"))
      (node (ref "MOTOR_02") (pin "A2") (pinfunction "A2_A2") (pintype "bidirectional"))
    )
    (net (code "22") (name "MA2_03") (class "Default")
      (node (ref "CM_03") (pin "2") (pinfunction "2_2") (pintype "bidirectional"))
      (node (ref "MOTOR_03") (pin "A2") (pinfunction "A2_A2") (pintype "bidirectional"))
    )
    (net (code "23") (name "MA2_04") (class "Default")
      (node (ref "CM_04") (pin "2") (pinfunction "2_2") (pintype "bidirectional"))
      (node (ref "MOTOR_04") (pin "A2") (pinfunction "A2_A2") (pintype "bidirectional"))
    )
    (net (code "24") (name "MA2_05") (class "Default")
      (node (ref "CM_05") (pin "2") (pinfunction "2_2") (pintype "bidirectional"))
      (node (ref "MOTOR_05") (pin "A2") (pinfunction "A2_A2") (pintype "bidirectional"))
    )
    (net (code "25") (name "MA2_06") (class "Default")
      (node (ref "CM_06") (pin "2") (pinfunction "2_2") (pintype "bidirectional"))
      (node (ref "MOTOR_06") (pin "A2") (pinfunction "A2_A2") (pintype "bidirectional"))
    )
    (net (code "26") (name "MA2_07") (class "Default")
      (node (ref "CM_07") (pin "2") (pinfunction "2_2") (pintype "bidirectional"))
      (node (ref "MOTOR_07") (pin "A2") (pinfunction "A2_A2") (pintype "bidirectional"))
    )
    (net (code "27") (name "MA2_08") (class "Default")
      (node (ref "CM_08") (pin "2") (pinfunction "2_2") (pintype "bidirectional"))
      (node (ref "MOTOR_08") (pin "A2") (pinfunction "A2_A2") (pintype "bidirectional"))
    )
    (net (code "28") (name "MB1_01") (class "Default")
      (node (ref "CM_01") (pin "4") (pinfunction "4_4") (pintype "bidirectional"))
      (node (ref "MOTOR_01") (pin "B1") (pinfunction "B1_B1") (pintype "bidirectional"))
    )
    (net (code "29") (name "MB1_02") (class "Default")
      (node (ref "CM_02") (pin "4") (pinfunction "4_4") (pintype "bidirectional"))
      (node (ref "MOTOR_02") (pin "B1") (pinfunction "B1_B1") (pintype "bidirectional"))
    )
    (net (code "30") (name "MB1_03") (class "Default")
      (node (ref "CM_03") (pin "4") (pinfunction "4_4") (pintype "bidirectional"))
      (node (ref "MOTOR_03") (pin "B1") (pinfunction "B1_B1") (pintype "bidirectional"))
    )
    (net (code "31") (name "MB1_04") (class "Default")
      (node (ref "CM_04") (pin "4") (pinfunction "4_4") (pintype "bidirectional"))
      (node (ref "MOTOR_04") (pin "B1") (pinfunction "B1_B1") (pintype "bidirectional"))
    )
    (net (code "32") (name "MB1_05") (class "Default")
      (node (ref "CM_05") (pin "4") (pinfunction "4_4") (pintype "bidirectional"))
      (node (ref "MOTOR_05") (pin "B1") (pinfunction "B1_B1") (pintype "bidirectional"))
    )
    (net (code "33") (name "MB1_06") (class "Default")
      (node (ref "CM_06") (pin "4") (pinfunction "4_4") (pintype "bidirectional"))
      (node (ref "MOTOR_06") (pin "B1") (pinfunction "B1_B1") (pintype "bidirectional"))
    )
    (net (code "34") (name "MB1_07") (class "Default")
      (node (ref "CM_07") (pin "4") (pinfunction "4_4") (pintype "bidirectional"))
      (node (ref "MOTOR_07") (pin "B1") (pinfunction "B1_B1") (pintype "bidirectional"))
    )
    (net (code "35") (name "MB1_08") (class "Default")
      (node (ref "CM_08") (pin "4") (pinfunction "4_4") (pintype "bidirectional"))
      (node (ref "MOTOR_08") (pin "B1") (pinfunction "B1_B1") (pintype "bidirectional"))
    )
    (net (code "36") (name "MB2_01") (class "Default")
      (node (ref "CM_01") (pin "3") (pinfunction "3_3") (pintype "bidirectional"))
      (node (ref "MOTOR_01") (pin "B2") (pinfunction "B2_B2") (pintype "bidirectional"))
    )
    (net (code "37") (name "MB2_02") (class "Default")
      (node (ref "CM_02") (pin "3") (pinfunction "3_3") (pintype "bidirectional"))
      (node (ref "MOTOR_02") (pin "B2") (pinfunction "B2_B2") (pintype "bidirectional"))
    )
    (net (code "38") (name "MB2_03") (class "Default")
      (node (ref "CM_03") (pin "3") (pinfunction "3_3") (pintype "bidirectional"))
      (node (ref "MOTOR_03") (pin "B2") (pinfunction "B2_B2") (pintype "bidirectional"))
    )
    (net (code "39") (name "MB2_04") (class "Default")
      (node (ref "CM_04") (pin "3") (pinfunction "3_3") (pintype "bidirectional"))
      (node (ref "MOTOR_04") (pin "B2") (pinfunction "B2_B2") (pintype "bidirectional"))
    )
    (net (code "40") (name "MB2_05") (class "Default")
      (node (ref "CM_05") (pin "3") (pinfunction "3_3") (pintype "bidirectional"))
      (node (ref "MOTOR_05") (pin "B2") (pinfunction "B2_B2") (pintype "bidirectional"))
    )
    (net (code "41") (name "MB2_06") (class "Default")
      (node (ref "CM_06") (pin "3") (pinfunction "3_3") (pintype "bidirectional"))
      (node (ref "MOTOR_06") (pin "B2") (pinfunction "B2_B2") (pintype "bidirectional"))
    )
    (net (code "42") (name "MB2_07") (class "Default")
      (node (ref "CM_07") (pin "3") (pinfunction "3_3") (pintype "bidirectional"))
      (node (ref "MOTOR_07") (pin "B2") (pinfunction "B2_B2") (pintype "bidirectional"))
    )
    (net (code "43") (name "MB2_08") (class "Default")
      (node (ref "CM_08") (pin "3") (pinfunction "3_3") (pintype "bidirectional"))
      (node (ref "MOTOR_08") (pin "B2") (pinfunction "B2_B2") (pintype "bidirectional"))
    )
    (net (code "44") (name "MDIR_01") (class "Default")
      (node (ref "MOTOR_01") (pin "DIR") (pinfunction "DIR_DIR") (pintype "bidirectional"))
      (node (ref "U$3") (pin "6") (pinfunction "6_6") (pintype "bidirectional"))
    )
    (net (code "45") (name "MDIR_02") (class "Default")
      (node (ref "MOTOR_02") (pin "DIR") (pinfunction "DIR_DIR") (pintype "bidirectional"))
      (node (ref "U$3") (pin "8") (pinfunction "8/TX2_8") (pintype "bidirectional"))
    )
    (net (code "46") (name "MDIR_03") (class "Default")
      (node (ref "MOTOR_03") (pin "DIR") (pinfunction "DIR_DIR") (pintype "bidirectional"))
      (node (ref "U$3") (pin "10") (pinfunction "10/CS_10") (pintype "bidirectional"))
    )
    (net (code "47") (name "MDIR_04") (class "Default")
      (node (ref "MOTOR_04") (pin "DIR") (pinfunction "DIR_DIR") (pintype "bidirectional"))
      (node (ref "U$3") (pin "12") (pinfunction "12/MISO_12") (pintype "bidirectional"))
    )
    (net (code "48") (name "MDIR_05") (class "Default")
      (node (ref "MOTOR_05") (pin "DIR") (pinfunction "DIR_DIR") (pintype "bidirectional"))
      (node (ref "U$3") (pin "17/A3") (pinfunction "17/A3/SDA1_17/A3") (pintype "bidirectional"))
    )
    (net (code "49") (name "MDIR_06") (class "Default")
      (node (ref "MOTOR_06") (pin "DIR") (pinfunction "DIR_DIR") (pintype "bidirectional"))
      (node (ref "U$3") (pin "3") (pinfunction "3_3") (pintype "bidirectional"))
    )
    (net (code "50") (name "MDIR_07") (class "Default")
      (node (ref "MOTOR_07") (pin "DIR") (pinfunction "DIR_DIR") (pintype "bidirectional"))
      (node (ref "U$3") (pin "23/A9") (pinfunction "23/A9/CRX1_23/A9") (pintype "bidirectional"))
    )
    (net (code "51") (name "MDIR_08") (class "Default")
      (node (ref "MOTOR_08") (pin "DIR") (pinfunction "DIR_DIR") (pintype "bidirectional"))
      (node (ref "U$3") (pin "27") (pinfunction "27/A13/SCK1_27") (pintype "bidirectional"))
    )
    (net (code "52") (name "MOTOR_MUX_RX") (class "Default")
      (node (ref "R15") (pin "1") (pinfunction "1_1") (pintype "passive"))
      (node (ref "U$3") (pin "21/A7") (pinfunction "21/A7/RX5_21/A7") (pintype "bidirectional"))
      (node (ref "U4") (pin "3") (pinfunction "Z_3") (pintype "bidirectional"))
    )
    (net (code "53") (name "MOTOR_MUX_TX") (class "Default")
      (node (ref "R15") (pin "2") (pinfunction "2_2") (pintype "passive"))
      (node (ref "U$3") (pin "20/A6") (pinfunction "20/A6/TX5_20/A6") (pintype "bidirectional"))
    )
    (net (code "54") (name "MOTOR_TX_RX_01") (class "Default")
      (node (ref "MOTOR_01") (pin "TX/RX") (pinfunction "TX/RX_TX/RX") (pintype "bidirectional"))
      (node (ref "U4") (pin "13") (pinfunction "Y0_13") (pintype "bidirectional"))
    )
    (net (code "55") (name "MOTOR_TX_RX_02") (class "Default")
      (node (ref "MOTOR_02") (pin "TX/RX") (pinfunction "TX/RX_TX/RX") (pintype "bidirectional"))
      (node (ref "U4") (pin "14") (pinfunction "Y1_14") (pintype "bidirectional"))
    )
    (net (code "56") (name "MOTOR_TX_RX_03") (class "Default")
      (node (ref "MOTOR_03") (pin "TX/RX") (pinfunction "TX/RX_TX/RX") (pintype "bidirectional"))
      (node (ref "U4") (pin "15") (pinfunction "Y2_15") (pintype "bidirectional"))
    )
    (net (code "57") (name "MOTOR_TX_RX_04") (class "Default")
      (node (ref "MOTOR_04") (pin "TX/RX") (pinfunction "TX/RX_TX/RX") (pintype "bidirectional"))
      (node (ref "U4") (pin "12") (pinfunction "Y3_12") (pintype "bidirectional"))
    )
    (net (code "58") (name "MOTOR_TX_RX_05") (class "Default")
      (node (ref "MOTOR_05") (pin "TX/RX") (pinfunction "TX/RX_TX/RX") (pintype "bidirectional"))
      (node (ref "U4") (pin "1") (pinfunction "Y4_1") (pintype "bidirectional"))
    )
    (net (code "59") (name "MOTOR_TX_RX_06") (class "Default")
      (node (ref "MOTOR_06") (pin "TX/RX") (pinfunction "TX/RX_TX/RX") (pintype "bidirectional"))
      (node (ref "U4") (pin "5") (pinfunction "Y5_5") (pintype "bidirectional"))
    )
    (net (code "60") (name "MOTOR_TX_RX_07") (class "Default")
      (node (ref "MOTOR_07") (pin "TX/RX") (pinfunction "TX/RX_TX/RX") (pintype "bidirectional"))
      (node (ref "U4") (pin "2") (pinfunction "Y6_2") (pintype "bidirectional"))
    )
    (net (code "61") (name "MOTOR_TX_RX_08") (class "Default")
      (node (ref "MOTOR_08") (pin "TX/RX") (pinfunction "TX/RX_TX/RX") (pintype "bidirectional"))
      (node (ref "U4") (pin "4") (pinfunction "Y7_4") (pintype "bidirectional"))
    )
    (net (code "62") (name "MSTEP_01") (class "Default")
      (node (ref "MOTOR_01") (pin "STEP") (pinfunction "STEP_STEP") (pintype "bidirectional"))
      (node (ref "U$3") (pin "5") (pinfunction "5_5") (pintype "bidirectional"))
    )
    (net (code "63") (name "MSTEP_02") (class "Default")
      (node (ref "MOTOR_02") (pin "STEP") (pinfunction "STEP_STEP") (pintype "bidirectional"))
      (node (ref "U$3") (pin "7") (pinfunction "7/RX2_7") (pintype "bidirectional"))
    )
    (net (code "64") (name "MSTEP_03") (class "Default")
      (node (ref "MOTOR_03") (pin "STEP") (pinfunction "STEP_STEP") (pintype "bidirectional"))
      (node (ref "U$3") (pin "9") (pinfunction "9_9") (pintype "bidirectional"))
    )
    (net (code "65") (name "MSTEP_04") (class "Default")
      (node (ref "MOTOR_04") (pin "STEP") (pinfunction "STEP_STEP") (pintype "bidirectional"))
      (node (ref "U$3") (pin "11") (pinfunction "11/MOSI_11") (pintype "bidirectional"))
    )
    (net (code "66") (name "MSTEP_05") (class "Default")
      (node (ref "MOTOR_05") (pin "STEP") (pinfunction "STEP_STEP") (pintype "bidirectional"))
      (node (ref "U$3") (pin "16/A2") (pinfunction "16/A2/SCL1_16/A2") (pintype "bidirectional"))
    )
    (net (code "67") (name "MSTEP_06") (class "Default")
      (node (ref "MOTOR_06") (pin "STEP") (pinfunction "STEP_STEP") (pintype "bidirectional"))
      (node (ref "U$3") (pin "2") (pinfunction "2_2") (pintype "bidirectional"))
    )
    (net (code "68") (name "MSTEP_07") (class "Default")
      (node (ref "MOTOR_07") (pin "STEP") (pinfunction "STEP_STEP") (pintype "bidirectional"))
      (node (ref "U$3") (pin "22/A8") (pinfunction "22/A8/CTX1_22/A8") (pintype "bidirectional"))
    )
    (net (code "69") (name "MSTEP_08") (class "Default")
      (node (ref "MOTOR_08") (pin "STEP") (pinfunction "STEP_STEP") (pintype "bidirectional"))
      (node (ref "U$3") (pin "26") (pinfunction "26/A12/MOSI1_26") (pintype "bidirectional"))
    )
    (net (code "70") (name "NEOPIXEL_01_3V") (class "Default")
      (node (ref "U$3") (pin "4") (pinfunction "4_4") (pintype "bidirectional"))
      (node (ref "U2") (pin "2") (pinfunction "A0_2") (pintype "bidirectional"))
    )
    (net (code "71") (name "NEOPIXEL_01_5V") (class "Default")
      (node (ref "P1") (pin "1") (pinfunction "1_1") (pintype "passive"))
      (node (ref "R7") (pin "2") (pinfunction "2_2") (pintype "passive"))
    )
    (net (code "72") (name "NEOPIXEL_02_3V") (class "Default")
      (node (ref "U$3") (pin "13") (pinfunction "13/SCK/LED_13") (pintype "bidirectional"))
      (node (ref "U2") (pin "3") (pinfunction "A1_3") (pintype "bidirectional"))
    )
    (net (code "73") (name "NEOPIXEL_02_5V") (class "Default")
      (node (ref "P1") (pin "3") (pinfunction "3_3") (pintype "passive"))
      (node (ref "R12") (pin "2") (pinfunction "2_2") (pintype "passive"))
    )
    (net (code "74") (name "NEOPIXEL_03_3V") (class "Default")
      (node (ref "U$3") (pin "14/A0") (pinfunction "14/A0/TX3_14/A0") (pintype "bidirectional"))
      (node (ref "U2") (pin "4") (pinfunction "A2_4") (pintype "bidirectional"))
    )
    (net (code "75") (name "NEOPIXEL_03_5V") (class "Default")
      (node (ref "P1") (pin "5") (pinfunction "5_5") (pintype "passive"))
      (node (ref "R13") (pin "2") (pinfunction "2_2") (pintype "passive"))
    )
    (net (code "76") (name "NEOPIXEL_04_3V") (class "Default")
      (node (ref "U$3") (pin "15/A1") (pinfunction "15/A1/RX3_15/A1") (pintype "bidirectional"))
      (node (ref "U2") (pin "5") (pinfunction "A3_5") (pintype "bidirectional"))
    )
    (net (code "77") (name "NEOPIXEL_04_5V") (class "Default")
      (node (ref "P1") (pin "7") (pinfunction "7_7") (pintype "passive"))
      (node (ref "R16") (pin "2") (pinfunction "2_2") (pintype "passive"))
    )
    (net (code "78") (name "NEOPIXEL_05_3V") (class "Default")
      (node (ref "U$3") (pin "24") (pinfunction "24/A10/SCL2_24") (pintype "bidirectional"))
      (node (ref "U2") (pin "6") (pinfunction "A4_6") (pintype "bidirectional"))
    )
    (net (code "79") (name "NEOPIXEL_05_5V") (class "Default")
      (node (ref "P1") (pin "9") (pinfunction "9_9") (pintype "passive"))
      (node (ref "R17") (pin "2") (pinfunction "2_2") (pintype "passive"))
    )
    (net (code "80") (name "NEOPIXEL_06_3V") (class "Default")
      (node (ref "U$3") (pin "25") (pinfunction "25/A11/SDA2_25") (pintype "bidirectional"))
      (node (ref "U2") (pin "7") (pinfunction "A5_7") (pintype "bidirectional"))
    )
    (net (code "81") (name "NEOPIXEL_06_5V") (class "Default")
      (node (ref "P1") (pin "11") (pinfunction "11_11") (pintype "passive"))
      (node (ref "R18") (pin "2") (pinfunction "2_2") (pintype "passive"))
    )
    (net (code "82") (name "NEOPIXEL_07_3V") (class "Default")
      (node (ref "U$3") (pin "28") (pinfunction "28/RX7_28") (pintype "bidirectional"))
      (node (ref "U2") (pin "8") (pinfunction "A6_8") (pintype "bidirectional"))
    )
    (net (code "83") (name "NEOPIXEL_07_5V") (class "Default")
      (node (ref "P1") (pin "13") (pinfunction "13_13") (pintype "passive"))
      (node (ref "R19") (pin "2") (pinfunction "2_2") (pintype "passive"))
    )
    (net (code "84") (name "NEOPIXEL_08_3V") (class "Default")
      (node (ref "U$3") (pin "29") (pinfunction "29/TX7_29") (pintype "bidirectional"))
      (node (ref "U2") (pin "9") (pinfunction "A7_9") (pintype "bidirectional"))
    )
    (net (code "85") (name "NEOPIXEL_08_5V") (class "Default")
      (node (ref "P1") (pin "15") (pinfunction "15_15") (pintype "passive"))
      (node (ref "R20") (pin "2") (pinfunction "2_2") (pintype "passive"))
    )
    (net (code "86") (name "Net-(CAN_INPUT-1)") (class "Default")
      (node (ref "CAN_INPUT") (pin "2") (pinfunction "1_2") (pintype "passive"))
      (node (ref "CAN_INPUT1") (pin "2") (pinfunction "1_2") (pintype "passive"))
      (node (ref "J2") (pin "2") (pinfunction "2_2") (pintype "passive"))
      (node (ref "MCP2562FD") (pin "6") (pinfunction "CANL_6") (pintype "input"))
      (node (ref "PES_D3") (pin "2") (pinfunction "2_2") (pintype "passive"))
    )
    (net (code "87") (name "Net-(CAN_INPUT-2)") (class "Default")
      (node (ref "CAN_INPUT") (pin "1") (pinfunction "2_1") (pintype "passive"))
      (node (ref "CAN_INPUT1") (pin "1") (pinfunction "2_1") (pintype "passive"))
      (node (ref "MCP2562FD") (pin "7") (pinfunction "CANH_7") (pintype "input"))
      (node (ref "PES_D3") (pin "1") (pinfunction "1_1") (pintype "passive"))
      (node (ref "R8") (pin "1") (pinfunction "1_1") (pintype "passive"))
    )
    (net (code "88") (name "Net-(CAN_INPUT4-1)") (class "Default")
      (node (ref "CAN_INPUT4") (pin "2") (pinfunction "1_2") (pintype "passive"))
      (node (ref "CAN_INPUT5") (pin "2") (pinfunction "1_2") (pintype "passive"))
      (node (ref "J3") (pin "2") (pinfunction "2_2") (pintype "passive"))
      (node (ref "MCP2562_2.0") (pin "6") (pinfunction "CANL_6") (pintype "input"))
      (node (ref "PES_D5") (pin "2") (pinfunction "2_2") (pintype "passive"))
    )
    (net (code "89") (name "Net-(CAN_INPUT4-2)") (class "Default")
      (node (ref "CAN_INPUT4") (pin "1") (pinfunction "2_1") (pintype "passive"))
      (node (ref "CAN_INPUT5") (pin "1") (pinfunction "2_1") (pintype "passive"))
      (node (ref "MCP2562_2.0") (pin "7") (pinfunction "CANH_7") (pintype "input"))
      (node (ref "PES_D5") (pin "1") (pinfunction "1_1") (pintype "passive"))
      (node (ref "R4") (pin "1") (pinfunction "1_1") (pintype "passive"))
    )
    (net (code "90") (name "Net-(D10-PadC)") (class "Default")
      (node (ref "D10") (pin "C") (pinfunction "C_C") (pintype "passive"))
      (node (ref "U$3") (pin "VIN") (pinfunction "VIN_VIN") (pintype "power_in"))
    )
    (net (code "91") (name "Net-(J2-Pad1)") (class "Default")
      (node (ref "J2") (pin "1") (pinfunction "1_1") (pintype "passive"))
      (node (ref "R8") (pin "2") (pinfunction "2_2") (pintype "passive"))
    )
    (net (code "92") (name "Net-(J3-Pad1)") (class "Default")
      (node (ref "J3") (pin "1") (pinfunction "1_1") (pintype "passive"))
      (node (ref "R4") (pin "2") (pinfunction "2_2") (pintype "passive"))
    )
    (net (code "93") (name "Net-(STATUS_LED-A)") (class "Default")
      (node (ref "R10") (pin "1") (pinfunction "1_1") (pintype "passive"))
      (node (ref "STATUS_LED") (pin "1") (pinfunction "A_1") (pintype "passive"))
    )
    (net (code "94") (name "Net-(U1-EN)") (class "Default")
      (node (ref "R9") (pin "2") (pinfunction "2_2") (pintype "passive"))
      (node (ref "U1") (pin "3") (pinfunction "EN_3") (pintype "bidirectional"))
    )
    (net (code "95") (name "Net-(U1-~{FAULT})") (class "Default")
      (node (ref "R11") (pin "2") (pinfunction "2_2") (pintype "passive"))
      (node (ref "U1") (pin "4") (pinfunction "~{FAULT}_4") (pintype "bidirectional"))
    )
    (net (code "96") (name "Net-(U2-B0)") (class "Default")
      (node (ref "R7") (pin "1") (pinfunction "1_1") (pintype "passive"))
      (node (ref "U2") (pin "18") (pinfunction "B0_18") (pintype "bidirectional"))
    )
    (net (code "97") (name "Net-(U2-B1)") (class "Default")
      (node (ref "R12") (pin "1") (pinfunction "1_1") (pintype "passive"))
      (node (ref "U2") (pin "17") (pinfunction "B1_17") (pintype "bidirectional"))
    )
    (net (code "98") (name "Net-(U2-B2)") (class "Default")
      (node (ref "R13") (pin "1") (pinfunction "1_1") (pintype "passive"))
      (node (ref "U2") (pin "16") (pinfunction "B2_16") (pintype "bidirectional"))
    )
    (net (code "99") (name "Net-(U2-B3)") (class "Default")
      (node (ref "R16") (pin "1") (pinfunction "1_1") (pintype "passive"))
      (node (ref "U2") (pin "15") (pinfunction "B3_15") (pintype "bidirectional"))
    )
    (net (code "100") (name "Net-(U2-B4)") (class "Default")
      (node (ref "R17") (pin "1") (pinfunction "1_1") (pintype "passive"))
      (node (ref "U2") (pin "14") (pinfunction "B4_14") (pintype "bidirectional"))
    )
    (net (code "101") (name "Net-(U2-B5)") (class "Default")
      (node (ref "R18") (pin "1") (pinfunction "1_1") (pintype "passive"))
      (node (ref "U2") (pin "13") (pinfunction "B5_13") (pintype "bidirectional"))
    )
    (net (code "102") (name "Net-(U2-B6)") (class "Default")
      (node (ref "R19") (pin "1") (pinfunction "1_1") (pintype "passive"))
      (node (ref "U2") (pin "12") (pinfunction "B6_12") (pintype "bidirectional"))
    )
    (net (code "103") (name "Net-(U2-B7)") (class "Default")
      (node (ref "R20") (pin "1") (pinfunction "1_1") (pintype "passive"))
      (node (ref "U2") (pin "11") (pinfunction "B7_11") (pintype "bidirectional"))
    )
    (net (code "104") (name "OSCIO") (class "Default")
      (node (ref "SX1509") (pin "11") (pinfunction "OSCIO_11") (pintype "bidirectional"))
    )
    (net (code "105") (name "RESET") (class "Default")
      (node (ref "P1") (pin "10") (pinfunction "10_10") (pintype "passive"))
      (node (ref "U$3") (pin "RESET") (pinfunction "RESET_RESET") (pintype "bidirectional"))
    )
    (net (code "106") (name "STATUS_PIN") (class "Default")
      (node (ref "P1") (pin "12") (pinfunction "12_12") (pintype "passive"))
      (node (ref "R10") (pin "2") (pinfunction "2_2") (pintype "passive"))
    )
    (net (code "107") (name "SX00_0") (class "Default")
      (node (ref "MOTOR_06") (pin "ENA") (pinfunction "ENABLE_ENA") (pintype "bidirectional"))
      (node (ref "SX1509") (pin "27") (pinfunction "I/O[0]_27") (pintype "bidirectional"))
    )
    (net (code "108") (name "SX00_1") (class "Default")
      (node (ref "J1") (pin "3") (pinfunction "3_3") (pintype "passive"))
      (node (ref "SX1509") (pin "28") (pinfunction "I/O[1]_28") (pintype "bidirectional"))
    )
    (net (code "109") (name "SX00_2") (class "Default")
      (node (ref "MOTOR_04") (pin "ENA") (pinfunction "ENABLE_ENA") (pintype "bidirectional"))
      (node (ref "SX1509") (pin "1") (pinfunction "I/O[2]_1") (pintype "bidirectional"))
    )
    (net (code "110") (name "SX00_3") (class "Default")
      (node (ref "J1") (pin "4") (pinfunction "4_4") (pintype "passive"))
      (node (ref "SX1509") (pin "2") (pinfunction "I/O[3]_2") (pintype "bidirectional"))
    )
    (net (code "111") (name "SX00_4") (class "Default")
      (node (ref "MOTOR_03") (pin "ENA") (pinfunction "ENABLE_ENA") (pintype "bidirectional"))
      (node (ref "SX1509") (pin "5") (pinfunction "I/O[4]_5") (pintype "bidirectional"))
    )
    (net (code "112") (name "SX00_5") (class "Default")
      (node (ref "J4") (pin "4") (pinfunction "4_4") (pintype "passive"))
      (node (ref "SX1509") (pin "6") (pinfunction "I/O[5]_6") (pintype "bidirectional"))
      (node (ref "U4") (pin "11") (pinfunction "S0_11") (pintype "bidirectional"))
    )
    (net (code "113") (name "SX00_6") (class "Default")
      (node (ref "MOTOR_02") (pin "ENA") (pinfunction "ENABLE_ENA") (pintype "bidirectional"))
      (node (ref "SX1509") (pin "7") (pinfunction "I/O[6]_7") (pintype "bidirectional"))
    )
    (net (code "114") (name "SX00_7") (class "Default")
      (node (ref "J4") (pin "5") (pinfunction "5_5") (pintype "passive"))
      (node (ref "SX1509") (pin "8") (pinfunction "I/O[7]_8") (pintype "bidirectional"))
      (node (ref "U4") (pin "10") (pinfunction "S1_10") (pintype "bidirectional"))
    )
    (net (code "115") (name "SX00_8") (class "Default")
      (node (ref "MOTOR_05") (pin "ENA") (pinfunction "ENABLE_ENA") (pintype "bidirectional"))
      (node (ref "SX1509") (pin "13") (pinfunction "I/O[8]_13") (pintype "bidirectional"))
    )
    (net (code "116") (name "SX00_9") (class "Default")
      (node (ref "J4") (pin "6") (pinfunction "6_6") (pintype "passive"))
      (node (ref "SX1509") (pin "14") (pinfunction "I/O[9]_14") (pintype "bidirectional"))
      (node (ref "U4") (pin "9") (pinfunction "S2_9") (pintype "bidirectional"))
    )
    (net (code "117") (name "SX00_10") (class "Default")
      (node (ref "MOTOR_01") (pin "ENA") (pinfunction "ENABLE_ENA") (pintype "bidirectional"))
      (node (ref "SX1509") (pin "15") (pinfunction "I/O[10]_15") (pintype "bidirectional"))
    )
    (net (code "118") (name "SX00_11") (class "Default")
      (node (ref "R14") (pin "1") (pinfunction "1_1") (pintype "passive"))
      (node (ref "SX1509") (pin "16") (pinfunction "I/O[11]_16") (pintype "bidirectional"))
      (node (ref "U4") (pin "6") (pinfunction "~{E}_6") (pintype "bidirectional"))
    )
    (net (code "119") (name "SX00_12") (class "Default")
      (node (ref "MOTOR_07") (pin "ENA") (pinfunction "ENABLE_ENA") (pintype "bidirectional"))
      (node (ref "SX1509") (pin "19") (pinfunction "I/O[12]_19") (pintype "bidirectional"))
    )
    (net (code "120") (name "SX00_13") (class "Default")
      (node (ref "J1") (pin "5") (pinfunction "5_5") (pintype "passive"))
      (node (ref "SX1509") (pin "20") (pinfunction "I/O[13]_20") (pintype "bidirectional"))
    )
    (net (code "121") (name "SX00_14") (class "Default")
      (node (ref "MOTOR_08") (pin "ENA") (pinfunction "ENABLE_ENA") (pintype "bidirectional"))
      (node (ref "SX1509") (pin "21") (pinfunction "I/O[14]_21") (pintype "bidirectional"))
    )
    (net (code "122") (name "SX00_15") (class "Default")
      (node (ref "J1") (pin "6") (pinfunction "6_6") (pintype "passive"))
      (node (ref "SX1509") (pin "22") (pinfunction "I/O[15]_22") (pintype "bidirectional"))
    )
    (net (code "123") (name "SX00_ADDR0") (class "Default")
      (node (ref "JP5") (pin "1") (pinfunction "1_1") (pintype "passive"))
      (node (ref "SX1509") (pin "26") (pinfunction "ADDR0_26") (pintype "bidirectional"))
    )
    (net (code "124") (name "SX00_ADDR1") (class "Default")
      (node (ref "JP6") (pin "2") (pinfunction "2_2") (pintype "passive"))
      (node (ref "SX1509") (pin "10") (pinfunction "ADDR1_10") (pintype "bidirectional"))
    )
    (net (code "125") (name "SX00_SCL") (class "Default")
      (node (ref "P1") (pin "4") (pinfunction "4_4") (pintype "passive"))
      (node (ref "R5") (pin "1") (pinfunction "1_1") (pintype "passive"))
      (node (ref "SX1509") (pin "25") (pinfunction "SCL_25") (pintype "bidirectional"))
      (node (ref "U$3") (pin "19/A5") (pinfunction "19/A5/SCL0_19/A5") (pintype "bidirectional"))
    )
    (net (code "126") (name "SX00_SDA") (class "Default")
      (node (ref "P1") (pin "2") (pinfunction "2_2") (pintype "passive"))
      (node (ref "R2") (pin "1") (pinfunction "1_1") (pintype "passive"))
      (node (ref "SX1509") (pin "24") (pinfunction "SDA_24") (pintype "bidirectional"))
      (node (ref "U$3") (pin "18/A4") (pinfunction "18/A4/SDA0_18/A4") (pintype "bidirectional"))
    )
    (net (code "127") (name "VBAT") (class "Default")
      (node (ref "U$3") (pin "VBAT") (pinfunction "VBAT_VBAT") (pintype "power_in"))
    )
    (net (code "128") (name "VCC_5VREG") (class "Default")
      (node (ref "C10") (pin "1") (pinfunction "1_1") (pintype "passive"))
      (node (ref "C11") (pin "1") (pinfunction "1_1") (pintype "passive"))
      (node (ref "C4") (pin "1") (pinfunction "1_1") (pintype "passive"))
      (node (ref "C8") (pin "1") (pinfunction "1_1") (pintype "passive"))
      (node (ref "D10") (pin "A") (pinfunction "A_A") (pintype "passive"))
      (node (ref "D2") (pin "A") (pinfunction "A_A") (pintype "passive"))
      (node (ref "D3") (pin "A") (pinfunction "A_A") (pintype "passive"))
      (node (ref "D4") (pin "A") (pinfunction "A_A") (pintype "passive"))
      (node (ref "D5") (pin "A") (pinfunction "A_A") (pintype "passive"))
      (node (ref "D6") (pin "A") (pinfunction "A_A") (pintype "passive"))
      (node (ref "D7") (pin "A") (pinfunction "A_A") (pintype "passive"))
      (node (ref "D8") (pin "A") (pinfunction "A_A") (pintype "passive"))
      (node (ref "D9") (pin "A") (pinfunction "A_A") (pintype "passive"))
      (node (ref "J1") (pin "2") (pinfunction "2_2") (pintype "passive"))
      (node (ref "J4") (pin "2") (pinfunction "2_2") (pintype "passive"))
      (node (ref "MCP2562FD") (pin "3") (pinfunction "VDD_3") (pintype "power_in"))
      (node (ref "MCP2562_2.0") (pin "3") (pinfunction "VDD_3") (pintype "power_in"))
      (node (ref "MOTOR_01") (pin "5V") (pinfunction "FAULT_5V") (pintype "bidirectional"))
      (node (ref "MOTOR_02") (pin "5V") (pinfunction "FAULT_5V") (pintype "bidirectional"))
      (node (ref "MOTOR_03") (pin "5V") (pinfunction "FAULT_5V") (pintype "bidirectional"))
      (node (ref "MOTOR_04") (pin "5V") (pinfunction "FAULT_5V") (pintype "bidirectional"))
      (node (ref "MOTOR_05") (pin "5V") (pinfunction "FAULT_5V") (pintype "bidirectional"))
      (node (ref "MOTOR_06") (pin "5V") (pinfunction "FAULT_5V") (pintype "bidirectional"))
      (node (ref "MOTOR_07") (pin "5V") (pinfunction "FAULT_5V") (pintype "bidirectional"))
      (node (ref "MOTOR_08") (pin "5V") (pinfunction "FAULT_5V") (pintype "bidirectional"))
      (node (ref "U1") (pin "6") (pinfunction "VOUT_6") (pintype "bidirectional"))
      (node (ref "U2") (pin "1") (pinfunction "DIR_1") (pintype "passive"))
      (node (ref "U2") (pin "20") (pinfunction "VCC_20") (pintype "power_in"))
      (node (ref "U4") (pin "16") (pinfunction "VCC_16") (pintype "bidirectional"))
      (node (ref "U4") (pin "EP") (pinfunction "VCC_EP") (pintype "bidirectional"))
    )
    (net (code "129") (name "VCC_LEDS") (class "Default")
      (node (ref "D1") (pin "C") (pinfunction "C_C") (pintype "passive"))
      (node (ref "P1") (pin "17") (pinfunction "17_17") (pintype "passive"))
      (node (ref "R1") (pin "1") (pinfunction "1_1") (pintype "passive"))
    )
    (net (code "130") (name "VCC_M") (class "Default")
      (node (ref "C12") (pin "2") (pinfunction "2_2") (pintype "passive"))
      (node (ref "C13") (pin "2") (pinfunction "2_2") (pintype "passive"))
      (node (ref "C14") (pin "2") (pinfunction "2_2") (pintype "passive"))
      (node (ref "C15") (pin "2") (pinfunction "2_2") (pintype "passive"))
      (node (ref "C16") (pin "2") (pinfunction "2_2") (pintype "passive"))
      (node (ref "C17") (pin "2") (pinfunction "2_2") (pintype "passive"))
      (node (ref "C18") (pin "2") (pinfunction "2_2") (pintype "passive"))
      (node (ref "C19") (pin "2") (pinfunction "2_2") (pintype "passive"))
      (node (ref "D2") (pin "C") (pinfunction "C_C") (pintype "passive"))
      (node (ref "D3") (pin "C") (pinfunction "C_C") (pintype "passive"))
      (node (ref "D4") (pin "C") (pinfunction "C_C") (pintype "passive"))
      (node (ref "D5") (pin "C") (pinfunction "C_C") (pintype "passive"))
      (node (ref "D6") (pin "C") (pinfunction "C_C") (pintype "passive"))
      (node (ref "D7") (pin "C") (pinfunction "C_C") (pintype "passive"))
      (node (ref "D8") (pin "C") (pinfunction "C_C") (pintype "passive"))
      (node (ref "D9") (pin "C") (pinfunction "C_C") (pintype "passive"))
      (node (ref "MC1") (pin "+") (pinfunction "+_+") (pintype "passive"))
      (node (ref "MC2") (pin "+") (pinfunction "+_+") (pintype "passive"))
      (node (ref "MC3") (pin "+") (pinfunction "+_+") (pintype "passive"))
      (node (ref "MC4") (pin "+") (pinfunction "+_+") (pintype "passive"))
      (node (ref "MC5") (pin "+") (pinfunction "+_+") (pintype "passive"))
      (node (ref "MC6") (pin "+") (pinfunction "+_+") (pintype "passive"))
      (node (ref "MC7") (pin "+") (pinfunction "+_+") (pintype "passive"))
      (node (ref "MC8") (pin "+") (pinfunction "+_+") (pintype "passive"))
      (node (ref "MOTOR_01") (pin "VM") (pinfunction "VM_VM") (pintype "bidirectional"))
      (node (ref "MOTOR_02") (pin "VM") (pinfunction "VM_VM") (pintype "bidirectional"))
      (node (ref "MOTOR_03") (pin "VM") (pinfunction "VM_VM") (pintype "bidirectional"))
      (node (ref "MOTOR_04") (pin "VM") (pinfunction "VM_VM") (pintype "bidirectional"))
      (node (ref "MOTOR_05") (pin "VM") (pinfunction "VM_VM") (pintype "bidirectional"))
      (node (ref "MOTOR_06") (pin "VM") (pinfunction "VM_VM") (pintype "bidirectional"))
      (node (ref "MOTOR_07") (pin "VM") (pinfunction "VM_VM") (pintype "bidirectional"))
      (node (ref "MOTOR_08") (pin "VM") (pinfunction "VM_VM") (pintype "bidirectional"))
      (node (ref "POWER_M") (pin "1") (pinfunction "1_1") (pintype "passive"))
    )
    (net (code "131") (name "VCC_MCU") (class "Default")
      (node (ref "POWER_MCU") (pin "1") (pinfunction "1_1") (pintype "passive"))
      (node (ref "U$1") (pin "VIN_1") (pinfunction "P$1_VIN_1") (pintype "bidirectional"))
      (node (ref "U$1") (pin "VIN_2") (pinfunction "P$1_VIN_2") (pintype "bidirectional"))
    )
    (net (code "132") (name "VCC_SWITCH") (class "Default")
      (node (ref "C1") (pin "1") (pinfunction "1_1") (pintype "passive"))
      (node (ref "C7") (pin "1") (pinfunction "1_1") (pintype "passive"))
      (node (ref "R1") (pin "2") (pinfunction "2_2") (pintype "passive"))
      (node (ref "R11") (pin "1") (pinfunction "1_1") (pintype "passive"))
      (node (ref "R9") (pin "1") (pinfunction "1_1") (pintype "passive"))
      (node (ref "U$1") (pin "VOUT_1") (pinfunction "P$4_VOUT_1") (pintype "bidirectional"))
      (node (ref "U$1") (pin "VOUT_2") (pinfunction "P$4_VOUT_2") (pintype "bidirectional"))
      (node (ref "U1") (pin "1") (pinfunction "VIN_1") (pintype "bidirectional"))
    )
    (net (code "133") (name "unconnected-(MOTOR_01-2-Pad9)") (class "Default")
      (node (ref "MOTOR_01") (pin "9") (pinfunction "2_9") (pintype "bidirectional"))
    )
    (net (code "134") (name "unconnected-(MOTOR_01-MODE1-PadMS1)") (class "Default")
      (node (ref "MOTOR_01") (pin "MS1") (pinfunction "MODE1_MS1") (pintype "bidirectional"))
    )
    (net (code "135") (name "unconnected-(MOTOR_01-MODE2-PadMS2)") (class "Default")
      (node (ref "MOTOR_01") (pin "MS2") (pinfunction "MODE2_MS2") (pintype "bidirectional"))
    )
    (net (code "136") (name "unconnected-(MOTOR_01-PadSTBY)") (class "Default")
      (node (ref "MOTOR_01") (pin "STBY") (pinfunction "STBY_STBY") (pintype "bidirectional"))
    )
    (net (code "137") (name "unconnected-(MOTOR_02-2-Pad9)") (class "Default")
      (node (ref "MOTOR_02") (pin "9") (pinfunction "2_9") (pintype "bidirectional"))
    )
    (net (code "138") (name "unconnected-(MOTOR_02-MODE1-PadMS1)") (class "Default")
      (node (ref "MOTOR_02") (pin "MS1") (pinfunction "MODE1_MS1") (pintype "bidirectional"))
    )
    (net (code "139") (name "unconnected-(MOTOR_02-MODE2-PadMS2)") (class "Default")
      (node (ref "MOTOR_02") (pin "MS2") (pinfunction "MODE2_MS2") (pintype "bidirectional"))
    )
    (net (code "140") (name "unconnected-(MOTOR_02-PadSTBY)") (class "Default")
      (node (ref "MOTOR_02") (pin "STBY") (pinfunction "STBY_STBY") (pintype "bidirectional"))
    )
    (net (code "141") (name "unconnected-(MOTOR_03-2-Pad9)") (class "Default")
      (node (ref "MOTOR_03") (pin "9") (pinfunction "2_9") (pintype "bidirectional"))
    )
    (net (code "142") (name "unconnected-(MOTOR_03-MODE1-PadMS1)") (class "Default")
      (node (ref "MOTOR_03") (pin "MS1") (pinfunction "MODE1_MS1") (pintype "bidirectional"))
    )
    (net (code "143") (name "unconnected-(MOTOR_03-MODE2-PadMS2)") (class "Default")
      (node (ref "MOTOR_03") (pin "MS2") (pinfunction "MODE2_MS2") (pintype "bidirectional"))
    )
    (net (code "144") (name "unconnected-(MOTOR_03-PadSTBY)") (class "Default")
      (node (ref "MOTOR_03") (pin "STBY") (pinfunction "STBY_STBY") (pintype "bidirectional"))
    )
    (net (code "145") (name "unconnected-(MOTOR_04-2-Pad9)") (class "Default")
      (node (ref "MOTOR_04") (pin "9") (pinfunction "2_9") (pintype "bidirectional"))
    )
    (net (code "146") (name "unconnected-(MOTOR_04-MODE1-PadMS1)") (class "Default")
      (node (ref "MOTOR_04") (pin "MS1") (pinfunction "MODE1_MS1") (pintype "bidirectional"))
    )
    (net (code "147") (name "unconnected-(MOTOR_04-MODE2-PadMS2)") (class "Default")
      (node (ref "MOTOR_04") (pin "MS2") (pinfunction "MODE2_MS2") (pintype "bidirectional"))
    )
    (net (code "148") (name "unconnected-(MOTOR_04-PadSTBY)") (class "Default")
      (node (ref "MOTOR_04") (pin "STBY") (pinfunction "STBY_STBY") (pintype "bidirectional"))
    )
    (net (code "149") (name "unconnected-(MOTOR_05-2-Pad9)") (class "Default")
      (node (ref "MOTOR_05") (pin "9") (pinfunction "2_9") (pintype "bidirectional"))
    )
    (net (code "150") (name "unconnected-(MOTOR_05-MODE1-PadMS1)") (class "Default")
      (node (ref "MOTOR_05") (pin "MS1") (pinfunction "MODE1_MS1") (pintype "bidirectional"))
    )
    (net (code "151") (name "unconnected-(MOTOR_05-MODE2-PadMS2)") (class "Default")
      (node (ref "MOTOR_05") (pin "MS2") (pinfunction "MODE2_MS2") (pintype "bidirectional"))
    )
    (net (code "152") (name "unconnected-(MOTOR_05-PadSTBY)") (class "Default")
      (node (ref "MOTOR_05") (pin "STBY") (pinfunction "STBY_STBY") (pintype "bidirectional"))
    )
    (net (code "153") (name "unconnected-(MOTOR_06-2-Pad9)") (class "Default")
      (node (ref "MOTOR_06") (pin "9") (pinfunction "2_9") (pintype "bidirectional"))
    )
    (net (code "154") (name "unconnected-(MOTOR_06-MODE1-PadMS1)") (class "Default")
      (node (ref "MOTOR_06") (pin "MS1") (pinfunction "MODE1_MS1") (pintype "bidirectional"))
    )
    (net (code "155") (name "unconnected-(MOTOR_06-MODE2-PadMS2)") (class "Default")
      (node (ref "MOTOR_06") (pin "MS2") (pinfunction "MODE2_MS2") (pintype "bidirectional"))
    )
    (net (code "156") (name "unconnected-(MOTOR_06-PadSTBY)") (class "Default")
      (node (ref "MOTOR_06") (pin "STBY") (pinfunction "STBY_STBY") (pintype "bidirectional"))
    )
    (net (code "157") (name "unconnected-(MOTOR_07-2-Pad9)") (class "Default")
      (node (ref "MOTOR_07") (pin "9") (pinfunction "2_9") (pintype "bidirectional"))
    )
    (net (code "158") (name "unconnected-(MOTOR_07-MODE1-PadMS1)") (class "Default")
      (node (ref "MOTOR_07") (pin "MS1") (pinfunction "MODE1_MS1") (pintype "bidirectional"))
    )
    (net (code "159") (name "unconnected-(MOTOR_07-MODE2-PadMS2)") (class "Default")
      (node (ref "MOTOR_07") (pin "MS2") (pinfunction "MODE2_MS2") (pintype "bidirectional"))
    )
    (net (code "160") (name "unconnected-(MOTOR_07-PadSTBY)") (class "Default")
      (node (ref "MOTOR_07") (pin "STBY") (pinfunction "STBY_STBY") (pintype "bidirectional"))
    )
    (net (code "161") (name "unconnected-(MOTOR_08-2-Pad9)") (class "Default")
      (node (ref "MOTOR_08") (pin "9") (pinfunction "2_9") (pintype "bidirectional"))
    )
    (net (code "162") (name "unconnected-(MOTOR_08-MODE1-PadMS1)") (class "Default")
      (node (ref "MOTOR_08") (pin "MS1") (pinfunction "MODE1_MS1") (pintype "bidirectional"))
    )
    (net (code "163") (name "unconnected-(MOTOR_08-MODE2-PadMS2)") (class "Default")
      (node (ref "MOTOR_08") (pin "MS2") (pinfunction "MODE2_MS2") (pintype "bidirectional"))
    )
    (net (code "164") (name "unconnected-(MOTOR_08-PadSTBY)") (class "Default")
      (node (ref "MOTOR_08") (pin "STBY") (pinfunction "STBY_STBY") (pintype "bidirectional"))
    )
    (net (code "165") (name "unconnected-(U$1-P$3-PadON)") (class "Default")
      (node (ref "U$1") (pin "ON") (pinfunction "P$3_ON") (pintype "bidirectional"))
    )
    (net (code "166") (name "unconnected-(U$1-P$6-PadGND_5)") (class "Default")
      (node (ref "U$1") (pin "GND_5") (pinfunction "P$6_GND_5") (pintype "bidirectional"))
    )
    (net (code "167") (name "unconnected-(U$3-PadPGM)") (class "Default")
      (node (ref "U$3") (pin "PGM") (pinfunction "PGM_PGM") (pintype "bidirectional"))
    )
    (net (code "168") (name "unconnected-(U1-CSLEW-Pad5)") (class "Default")
      (node (ref "U1") (pin "5") (pinfunction "CSLEW_5") (pintype "bidirectional"))
    )
    (net (code "169") (name "~{RESET}") (class "Default")
      (node (ref "R3") (pin "1") (pinfunction "1_1") (pintype "passive"))
      (node (ref "SX1509") (pin "23") (pinfunction "~{RESET}_23") (pintype "bidirectional"))
    )
  )
)
